# Sheet2.net
KiCad netlist of a schematic drawn in Altium Designer
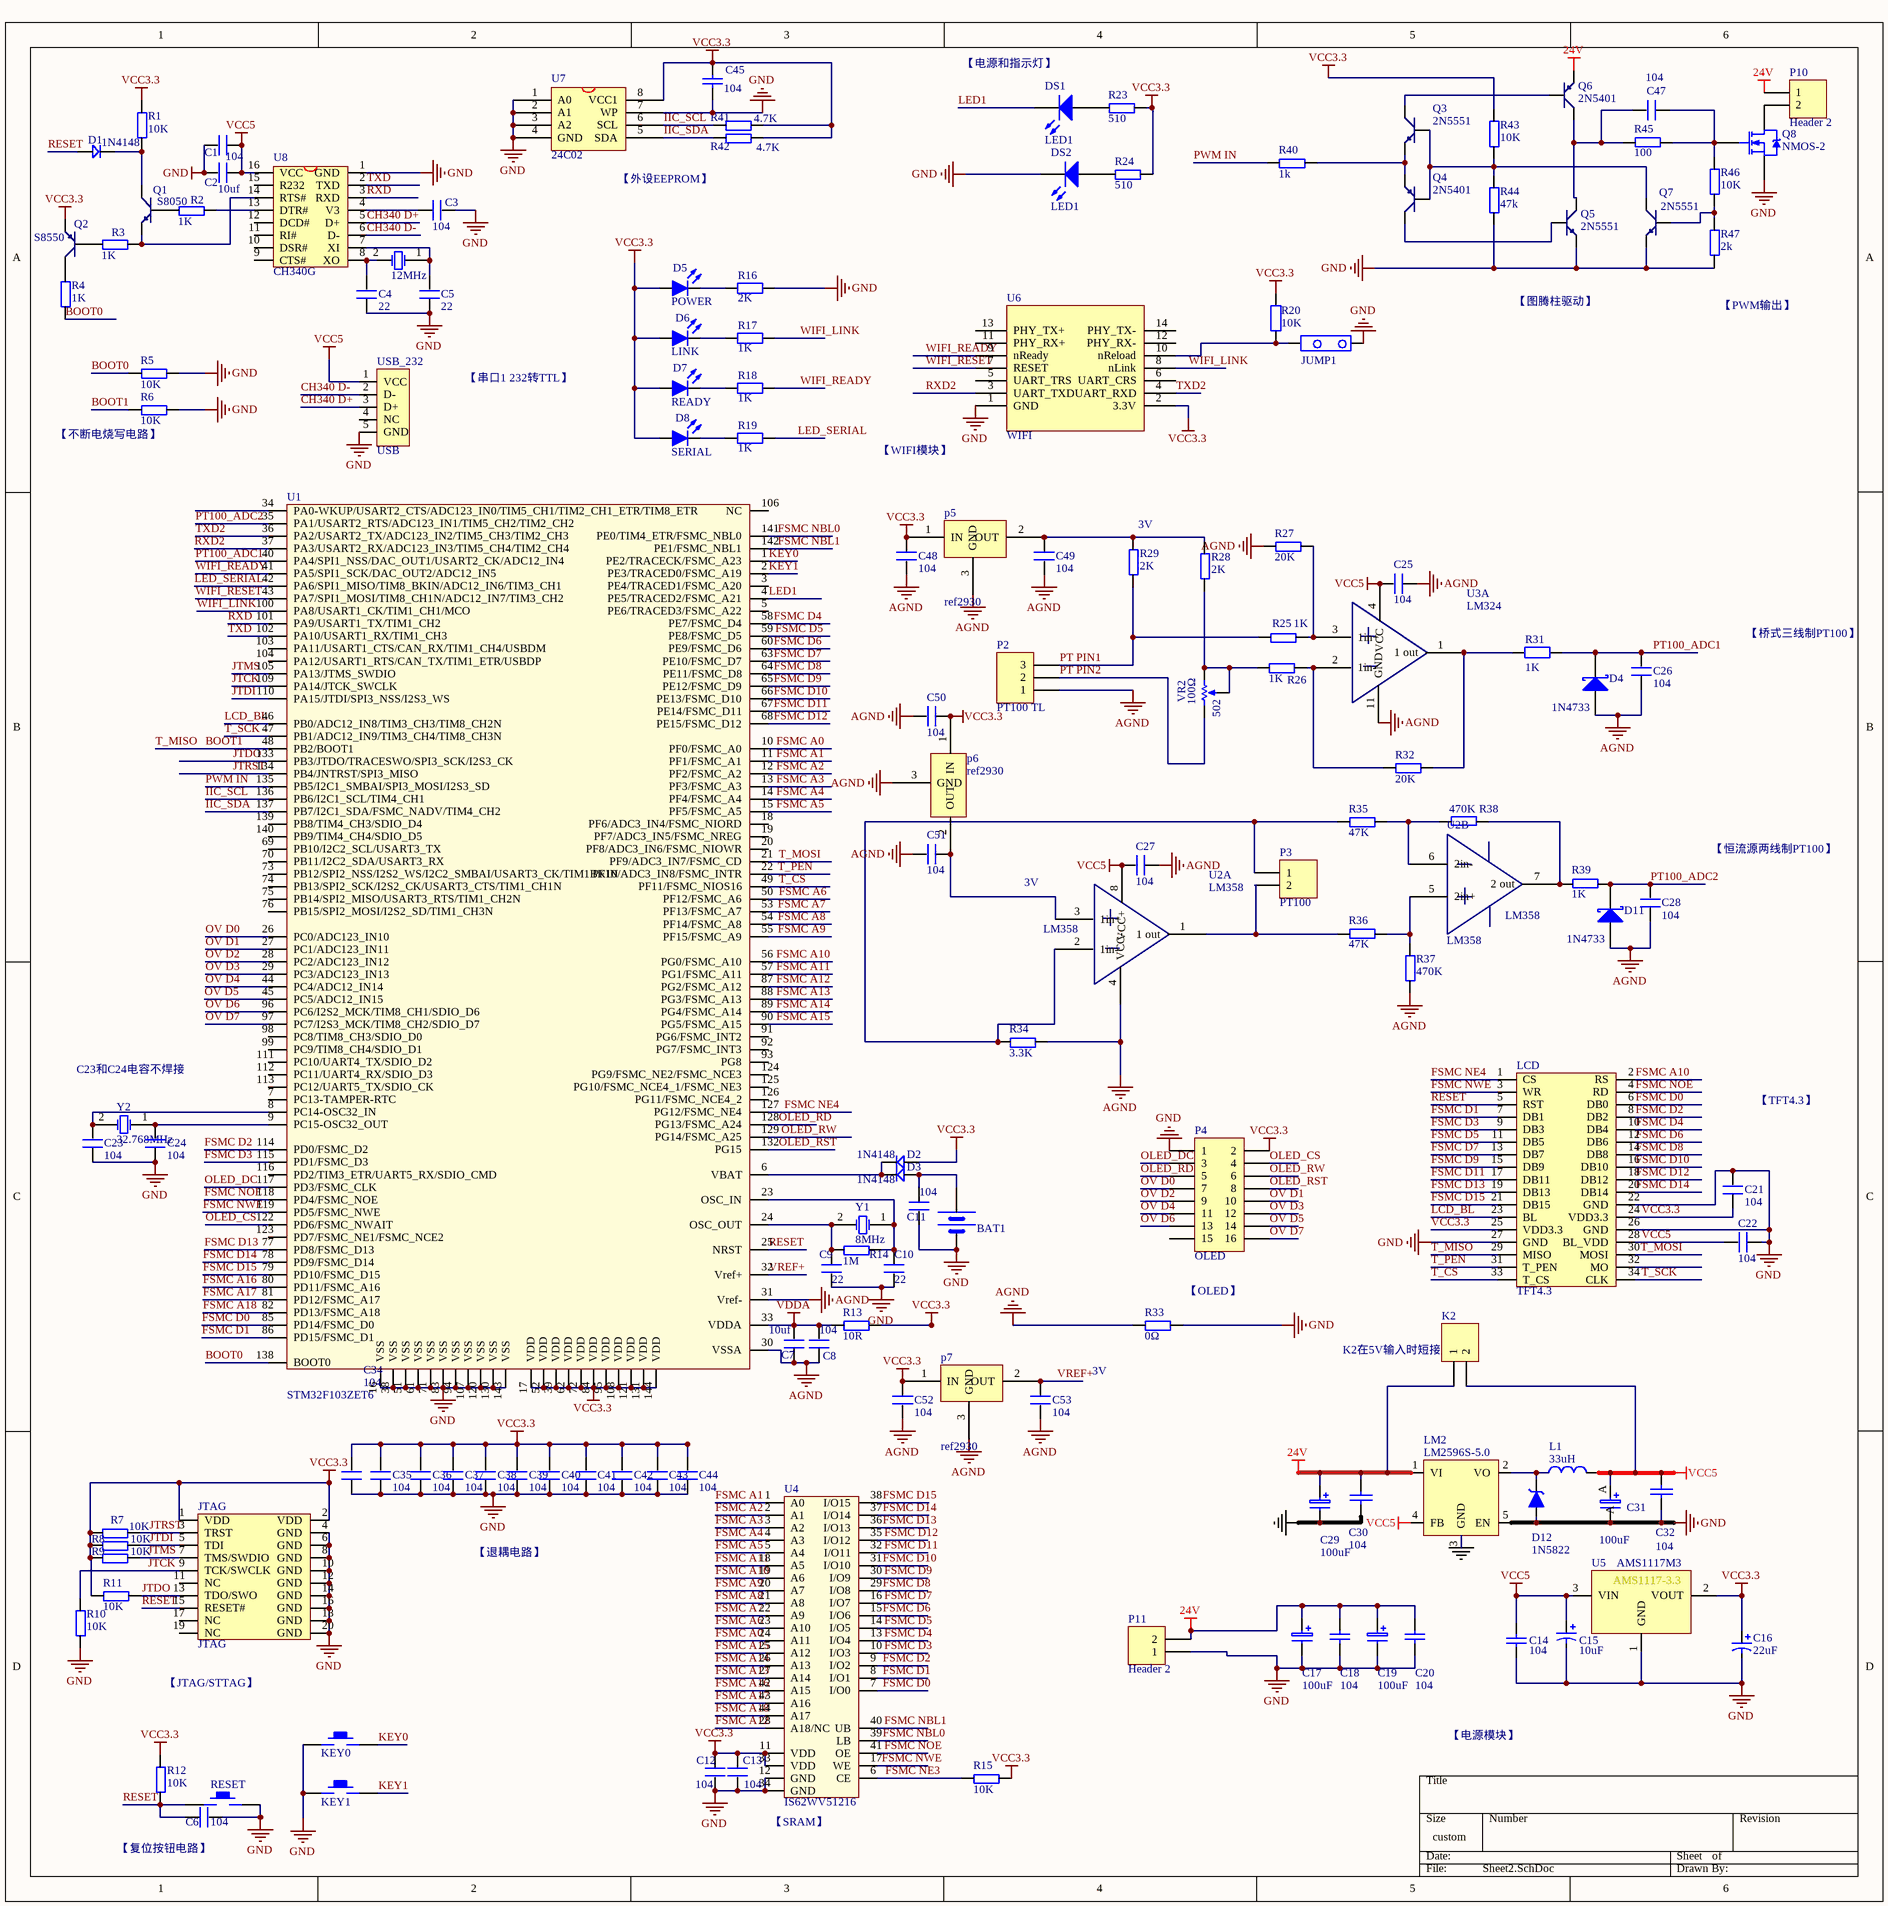
[diagram p0: Sheet2.SchDoc]

(export (version "E")
  (design (tool "Eeschema 10.0.6"))
  (components
    (comp (ref "BAT1") (value "BATT") (footprint "BATM") (libsource (lib "WARSHIP") (part "BAT")))
    (comp (ref "C1") (value "104") (footprint "0805") (libsource (lib "WARSHIP") (part "C")))
    (comp (ref "C2") (value "10uf") (footprint "0805") (libsource (lib "WARSHIP") (part "C")))
    (comp (ref "C3") (value "104") (footprint "0805") (libsource (lib "WARSHIP") (part "C")))
    (comp (ref "C4") (value "22") (footprint "0805") (libsource (lib "WARSHIP") (part "C")))
    (comp (ref "C5") (value "22") (footprint "0805") (libsource (lib "WARSHIP") (part "C")))
    (comp (ref "C6") (value "104") (footprint "0805") (libsource (lib "WARSHIP") (part "C")))
    (comp (ref "C7") (value "10uf") (footprint "0805") (libsource (lib "WARSHIP") (part "C")))
    (comp (ref "C8") (value "104") (footprint "0805") (libsource (lib "WARSHIP") (part "C")))
    (comp (ref "C9") (value "22") (footprint "0805") (libsource (lib "WARSHIP") (part "C")))
    (comp (ref "C10") (value "22") (footprint "0805") (libsource (lib "WARSHIP") (part "C")))
    (comp (ref "C11") (value "104") (footprint "0805") (libsource (lib "WARSHIP") (part "C")))
    (comp (ref "C12") (value "104") (footprint "0805") (libsource (lib "WARSHIP") (part "C")))
    (comp (ref "C13") (value "104") (footprint "0805") (libsource (lib "WARSHIP") (part "C")))
    (comp (ref "C14") (value "104") (footprint "0805") (libsource (lib "") (part "Cap1_1")))
    (comp (ref "C15")
      (value "10uF")
      (footprint "CASE-3216A")
      (libsource (lib "MySchematicLib") (part "Cap2"))
    )
    (comp (ref "C16")
      (value "22uF")
      (footprint "RVT 22UF 25V")
      (libsource (lib "MySchematicLib") (part "Cap2"))
    )
    (comp (ref "C17") (value "100uF") (footprint "CC8*10.5") (libsource (lib "MySchematicLib") (part "Cap3")))
    (comp (ref "C18") (value "104") (footprint "0805") (libsource (lib "MySchematicLib") (part "Cap1")))
    (comp (ref "C19") (value "100uF") (footprint "CC8*10.5") (libsource (lib "MySchematicLib") (part "Cap3")))
    (comp (ref "C20") (value "104") (footprint "0805") (libsource (lib "MySchematicLib") (part "Cap1")))
    (comp (ref "C21") (value "104") (footprint "0805") (libsource (lib "WARSHIP") (part "C")))
    (comp (ref "C22") (value "104") (footprint "0805") (libsource (lib "WARSHIP") (part "C")))
    (comp (ref "C23") (value "104") (footprint "0805") (libsource (lib "WARSHIP") (part "C")))
    (comp (ref "C24") (value "104") (footprint "0805") (libsource (lib "WARSHIP") (part "C")))
    (comp (ref "C25") (value "104") (footprint "0805") (libsource (lib "WARSHIP") (part "C")))
    (comp (ref "C26") (value "104") (footprint "0805") (libsource (lib "WARSHIP") (part "C")))
    (comp (ref "C27") (value "104") (footprint "0805") (libsource (lib "WARSHIP") (part "C")))
    (comp (ref "C28") (value "104") (footprint "0805") (libsource (lib "WARSHIP") (part "C")))
    (comp (ref "C29") (value "100uF") (footprint "CC8*10.5") (libsource (lib "MySchematicLib") (part "Cap3")))
    (comp (ref "C30") (value "104") (footprint "0805") (libsource (lib "*") (part "CAP")))
    (comp (ref "C31") (value "100uF") (footprint "rvt 100uf /25V") (libsource (lib "") (part "Cap3_1")))
    (comp (ref "C32") (value "104") (footprint "0805") (libsource (lib "") (part "CAP_1")))
    (comp (ref "C34") (value "104") (footprint "0805") (libsource (lib "WARSHIP") (part "C")))
    (comp (ref "C35") (value "104") (footprint "0805") (libsource (lib "WARSHIP") (part "C")))
    (comp (ref "C36") (value "104") (footprint "0805") (libsource (lib "WARSHIP") (part "C")))
    (comp (ref "C37") (value "104") (footprint "0805") (libsource (lib "WARSHIP") (part "C")))
    (comp (ref "C38") (value "104") (footprint "0805") (libsource (lib "WARSHIP") (part "C")))
    (comp (ref "C39") (value "104") (footprint "0805") (libsource (lib "WARSHIP") (part "C")))
    (comp (ref "C40") (value "104") (footprint "0805") (libsource (lib "WARSHIP") (part "C")))
    (comp (ref "C41") (value "104") (footprint "0805") (libsource (lib "WARSHIP") (part "C")))
    (comp (ref "C42") (value "104") (footprint "0805") (libsource (lib "WARSHIP") (part "C")))
    (comp (ref "C43") (value "104") (footprint "0805") (libsource (lib "WARSHIP") (part "C")))
    (comp (ref "C44") (value "104") (footprint "0805") (libsource (lib "WARSHIP") (part "C")))
    (comp (ref "C45")
      (value "104")
      (footprint "0805")
      (description "Capacitor")
      (fields (field (name "Comment") "Cap") (field (name "PUBLISHER") "Altium Limited"))
      (libsource (lib "Miscellaneous Devices") (part "Cap"))
    )
    (comp (ref "C47") (value "104") (footprint "0805") (libsource (lib "WARSHIP") (part "C")))
    (comp (ref "C48") (value "104") (footprint "0805") (libsource (lib "WARSHIP") (part "C")))
    (comp (ref "C49") (value "104") (footprint "0805") (libsource (lib "WARSHIP") (part "C")))
    (comp (ref "C50") (value "104") (footprint "0805") (libsource (lib "WARSHIP") (part "C")))
    (comp (ref "C51") (value "104") (footprint "0805") (libsource (lib "WARSHIP") (part "C")))
    (comp (ref "C52") (value "104") (footprint "0805") (libsource (lib "WARSHIP") (part "C")))
    (comp (ref "C53") (value "104") (footprint "0805") (libsource (lib "WARSHIP") (part "C")))
    (comp (ref "D1") (value "1N4148") (footprint "DIODE_SOP") (libsource (lib "WARSHIP") (part "D")))
    (comp (ref "D2") (value "1N4148") (footprint "DIODE_SOP") (libsource (lib "WARSHIP") (part "D")))
    (comp (ref "D3") (value "1N4148") (footprint "DIODE_SOP") (libsource (lib "WARSHIP") (part "D")))
    (comp (ref "D4")
      (value "1N4733")
      (footprint "LC-DO-41")
      (description "Schottky Rectifier")
      (fields (field (name "PUBLISHER") "Altium Limited"))
      (libsource (lib "") (part "Diode 18TQ045_1"))
    )
    (comp (ref "D5") (value "POWER") (footprint "SMDLED") (libsource (lib "MySchematicLib") (part "LED1")))
    (comp (ref "D6") (value "LINK") (footprint "SMDLED") (libsource (lib "MySchematicLib") (part "LED1")))
    (comp (ref "D7") (value "READY") (footprint "SMDLED") (libsource (lib "MySchematicLib") (part "LED1")))
    (comp (ref "D8") (value "SERIAL") (footprint "SMDLED") (libsource (lib "MySchematicLib") (part "LED1")))
    (comp (ref "D11")
      (value "1N4733")
      (footprint "LC-DO-41")
      (description "Schottky Rectifier")
      (fields (field (name "PUBLISHER") "Altium Limited"))
      (libsource (lib "Miscellaneous Devices") (part "Diode 18TQ045"))
    )
    (comp (ref "D12")
      (value "1N5822")
      (footprint "1n5822")
      (description "Zener Diode")
      (libsource (lib "*") (part "ZENER3"))
    )
    (comp (ref "DS1")
      (value "LED1")
      (footprint "SMDLED")
      (description "Typical RED, GREEN, YELLOW, AMBER GaAs LED")
      (fields (field (name "PUBLISHER") "Altium Limited"))
      (libsource (lib "WARSHIP") (part "LED2"))
    )
    (comp (ref "DS2")
      (value "LED1")
      (footprint "SMDLED")
      (description "Typical RED, GREEN, YELLOW, AMBER GaAs LED")
      (fields (field (name "PUBLISHER") "Altium Limited"))
      (libsource (lib "WARSHIP") (part "LED2"))
    )
    (comp (ref "JTAG") (value "JTAG") (footprint "JTAG_20") (libsource (lib "WARSHIP") (part "JTAG")))
    (comp (ref "JUMP1")
      (value "Jumper")
      (footprint "HDR1X2")
      (libsource (lib "MySchematicLib") (part "Jumper"))
    )
    (comp (ref "K2")
      (value "Header 2")
      (footprint "HDR1X2")
      (description "Header, 2-Pin")
      (fields (field (name "PUBLISHER") "Altium Limited"))
      (libsource (lib "") (part "Header 2_2"))
    )
    (comp (ref "KEY0") (value "KEY_M") (footprint "KEY_M") (libsource (lib "WARSHIP") (part "KEY_M")))
    (comp (ref "KEY1") (value "KEY_M") (footprint "KEY_M") (libsource (lib "WARSHIP") (part "KEY_M")))
    (comp (ref "L1") (value "33uH") (footprint "100UH") (libsource (lib "*") (part "L")))
    (comp (ref "LCD")
      (value "TFT4.3")
      (footprint "DB2*17-3.5")
      (libsource (lib "4.3TFTLCD") (part "TFT_LCD2"))
    )
    (comp (ref "LM2") (value "LM2596S-5.0") (footprint "LM2596S-5.0") (libsource (lib "*") (part "12V-5V")))
    (comp (ref "P2")
      (value "PT100 TL")
      (footprint "3SPI")
      (description "Header, 3-Pin")
      (fields (field (name "PUBLISHER") "Altium Limited"))
      (libsource (lib "Miscellaneous Connectors") (part "Header 3"))
    )
    (comp (ref "P3")
      (value "PT100")
      (footprint "2SPI")
      (description "Header, 2-Pin")
      (fields (field (name "PUBLISHER") "Altium Limited"))
      (libsource (lib "") (part "Header 2_1"))
    )
    (comp (ref "P4")
      (value "OLED")
      (footprint "HDR2X8")
      (description "Header, 8-Pin, Dual row")
      (fields (field (name "PUBLISHER") "Altium Limited"))
      (libsource (lib "OLED模块封装库") (part "Header 8X2"))
    )
    (comp (ref "p5")
      (value "ref2930")
      (footprint "LC-SOT-23(SOT-23-3)")
      (libsource (lib "ref2930aid") (part "ref2930"))
    )
    (comp (ref "p6")
      (value "ref2930")
      (footprint "LC-SOT-23(SOT-23-3)")
      (libsource (lib "") (part "ref2930_1"))
    )
    (comp (ref "p7")
      (value "ref2930")
      (footprint "LC-SOT-23(SOT-23-3)")
      (libsource (lib "ref2930aid") (part "ref2930"))
    )
    (comp (ref "P10")
      (value "Header 2")
      (footprint "2SPI")
      (description "Header, 2-Pin")
      (fields (field (name "PUBLISHER") "Altium Limited"))
      (libsource (lib "") (part "Header 2_1"))
    )
    (comp (ref "P11")
      (value "Header 2")
      (footprint "2SPI")
      (description "Header, 2-Pin")
      (fields (field (name "PUBLISHER") "Altium Limited"))
      (libsource (lib "Miscellaneous Connectors") (part "Header 2"))
    )
    (comp (ref "Q1")
      (value "S8050")
      (footprint "SOT-23R")
      (description "8050/BCW846/BCW847")
      (libsource (lib "WARSHIP") (part "NPN"))
    )
    (comp (ref "Q2")
      (value "S8550")
      (footprint "SOT-23R")
      (description "8550/BCW68")
      (libsource (lib "WARSHIP") (part "PNP"))
    )
    (comp (ref "Q3")
      (value "2N5551")
      (footprint "SOT-23R")
      (description "8050/BCW846/BCW847")
      (libsource (lib "WARSHIP") (part "NPN"))
    )
    (comp (ref "Q4")
      (value "2N5401")
      (footprint "SOT-23R")
      (description "8550/BCW68")
      (libsource (lib "WARSHIP") (part "PNP"))
    )
    (comp (ref "Q5")
      (value "2N5551")
      (footprint "SOT-23R")
      (description "8050/BCW846/BCW847")
      (libsource (lib "WARSHIP") (part "NPN"))
    )
    (comp (ref "Q6")
      (value "2N5401")
      (footprint "SOT-23R")
      (description "8550/BCW68")
      (libsource (lib "WARSHIP") (part "PNP"))
    )
    (comp (ref "Q7")
      (value "2N5551")
      (footprint "SOT-23R")
      (description "8050/BCW846/BCW847")
      (libsource (lib "WARSHIP") (part "NPN"))
    )
    (comp (ref "Q8")
      (value "NMOS-2")
      (footprint "LC-TO-263-2")
      (description "N-Channel Power MOSFET")
      (fields (field (name "PUBLISHER") "Altium Limited"))
      (libsource (lib "Miscellaneous Devices") (part "NMOS-2"))
    )
    (comp (ref "R1") (value "10K") (footprint "0805") (libsource (lib "WARSHIP") (part "R")))
    (comp (ref "R2") (value "1K") (footprint "0805") (libsource (lib "WARSHIP") (part "R")))
    (comp (ref "R3") (value "1K") (footprint "0805") (libsource (lib "WARSHIP") (part "R")))
    (comp (ref "R4") (value "1K") (footprint "0805") (libsource (lib "WARSHIP") (part "R")))
    (comp (ref "R5") (value "10K") (footprint "0805") (libsource (lib "WARSHIP") (part "R")))
    (comp (ref "R6") (value "10K") (footprint "0805") (libsource (lib "WARSHIP") (part "R")))
    (comp (ref "R7") (value "10K") (footprint "0805") (libsource (lib "WARSHIP") (part "R")))
    (comp (ref "R8") (value "10K") (footprint "0805") (libsource (lib "WARSHIP") (part "R")))
    (comp (ref "R9") (value "10K") (footprint "0805") (libsource (lib "WARSHIP") (part "R")))
    (comp (ref "R10") (value "10K") (footprint "0805") (libsource (lib "WARSHIP") (part "R")))
    (comp (ref "R11") (value "10K") (footprint "0805") (libsource (lib "WARSHIP") (part "R")))
    (comp (ref "R12") (value "10K") (footprint "0805") (libsource (lib "WARSHIP") (part "R")))
    (comp (ref "R13") (value "10R") (footprint "0805") (libsource (lib "WARSHIP") (part "R")))
    (comp (ref "R14") (value "1M") (footprint "0805") (libsource (lib "WARSHIP") (part "R")))
    (comp (ref "R15") (value "10K") (footprint "0805") (libsource (lib "WARSHIP") (part "R")))
    (comp (ref "R16") (value "2K") (footprint "0805") (libsource (lib "") (part "Res1_1")))
    (comp (ref "R17") (value "1K") (footprint "0805") (libsource (lib "") (part "Res1_1")))
    (comp (ref "R18") (value "1K") (footprint "0805") (libsource (lib "") (part "Res1_1")))
    (comp (ref "R19") (value "1K") (footprint "0805") (libsource (lib "") (part "Res1_1")))
    (comp (ref "R20") (value "10K") (footprint "0805") (libsource (lib "MySchematicLib") (part "Res1")))
    (comp (ref "R23") (value "510") (footprint "0805") (libsource (lib "WARSHIP") (part "R")))
    (comp (ref "R24") (value "510") (footprint "0805") (libsource (lib "WARSHIP") (part "R")))
    (comp (ref "R25") (value "1K") (footprint "0805") (libsource (lib "WARSHIP") (part "R")))
    (comp (ref "R26") (value "1K") (footprint "0805") (libsource (lib "WARSHIP") (part "R")))
    (comp (ref "R27") (value "20K") (footprint "0805") (libsource (lib "WARSHIP") (part "R")))
    (comp (ref "R28") (value "2K") (footprint "0805") (libsource (lib "WARSHIP") (part "R")))
    (comp (ref "R29") (value "2K") (footprint "0805") (libsource (lib "WARSHIP") (part "R")))
    (comp (ref "R31")
      (value "1K")
      (footprint "0805")
      (description "Resistor")
      (fields (field (name "Comment") "Res2") (field (name "PUBLISHER") "Altium Limited"))
      (libsource (lib "Miscellaneous Devices") (part "Res2"))
    )
    (comp (ref "R32") (value "20K") (footprint "0805") (libsource (lib "WARSHIP") (part "R")))
    (comp (ref "R33") (value "0Ω") (footprint "0805") (libsource (lib "WARSHIP") (part "R")))
    (comp (ref "R34") (value "3.3K") (footprint "0805") (libsource (lib "WARSHIP") (part "R")))
    (comp (ref "R35") (value "47K") (footprint "0805") (libsource (lib "WARSHIP") (part "R")))
    (comp (ref "R36") (value "47K") (footprint "0805") (libsource (lib "WARSHIP") (part "R")))
    (comp (ref "R37") (value "470K") (footprint "0805") (libsource (lib "WARSHIP") (part "R")))
    (comp (ref "R38") (value "470K") (footprint "0805") (libsource (lib "WARSHIP") (part "R")))
    (comp (ref "R39") (value "1K") (footprint "0805") (libsource (lib "WARSHIP") (part "R")))
    (comp (ref "R40") (value "1k") (footprint "0805") (libsource (lib "WARSHIP") (part "R")))
    (comp (ref "R41") (value "4.7K") (footprint "0805") (libsource (lib "WARSHIP") (part "R")))
    (comp (ref "R42") (value "4.7K") (footprint "0805") (libsource (lib "WARSHIP") (part "R")))
    (comp (ref "R43") (value "10K") (footprint "0805") (libsource (lib "WARSHIP") (part "R")))
    (comp (ref "R44") (value "47k") (footprint "0805") (libsource (lib "WARSHIP") (part "R")))
    (comp (ref "R45") (value "100") (footprint "0805") (libsource (lib "WARSHIP") (part "R")))
    (comp (ref "R46") (value "10K") (footprint "0805") (libsource (lib "WARSHIP") (part "R")))
    (comp (ref "R47") (value "2k") (footprint "0805") (libsource (lib "WARSHIP") (part "R")))
    (comp (ref "RESET") (value "KEY_M") (footprint "KEY_M") (libsource (lib "WARSHIP") (part "KEY_M")))
    (comp (ref "U1")
      (value "STM32F103ZET6")
      (footprint "LQFP144")
      (libsource (lib "WARSHIP") (part "STM32F103ZET6"))
    )
    (comp (ref "U2") (value "LM358") (footprint "LC-MSOP-8") (libsource (lib "LM358") (part "LM358")))
    (comp (ref "U3") (value "LM324") (footprint "LC-DIP-14") (libsource (lib "LM324") (part "LM324")))
    (comp (ref "U4")
      (value "IS62WV51216")
      (footprint "TSOP44")
      (libsource (lib "WARSHIP") (part "IS61LV51216"))
    )
    (comp (ref "U5")
      (value "AMS1117M3")
      (footprint "LC-SOT-223")
      (libsource (lib "MySchematicLib") (part "AMS1117-3.3"))
    )
    (comp (ref "U6")
      (value "WIFI")
      (footprint "USR-WIFI232")
      (libsource (lib "Communication Module") (part "USR-WIFI232-ABD"))
    )
    (comp (ref "U7") (value "24C02") (footprint "SOP-8") (libsource (lib "WARSHIP") (part "24C256")))
    (comp (ref "U8")
      (value "CH340G")
      (footprint "SOP16M")
      (description "USB2UART")
      (libsource (lib "WARSHIP") (part "CH340G"))
    )
    (comp (ref "USB_232") (value "USB") (footprint "USB/SM0.8-6H5") (libsource (lib "WARSHIP") (part "USB5")))
    (comp (ref "VR2")
      (value "502")
      (footprint "503")
      (description "Potentiometer")
      (fields (field (name "ALTIUM_VALUE") "100Ω") (field (name "PUBLISHER") "Altium Limited"))
      (libsource (lib "Miscellaneous Devices") (part "RPot"))
    )
    (comp (ref "Y1")
      (value "8MHz")
      (footprint "XTAL_US")
      (description "Crystal Oscillator")
      (fields (field (name "PUBLISHER") "Altium Limited"))
      (libsource (lib "WARSHIP") (part "XTAL"))
    )
    (comp (ref "Y2")
      (value "32.768MHz")
      (footprint "XTAL32")
      (description "Crystal Oscillator")
      (fields (field (name "PUBLISHER") "Altium Limited"))
      (libsource (lib "WARSHIP") (part "XTAL"))
    )
    (comp (ref "Y3")
      (value "12MHz")
      (footprint "XTAL_US")
      (description "Crystal Oscillator")
      (fields (field (name "PUBLISHER") "Altium Limited"))
      (libsource (lib "WARSHIP") (part "XTAL"))
    )
  )
  (nets
    (net (code "1") (name "/BOOT0") (class "Default")
      (node (ref "R4") (pin "1") (pintype "passive"))
      (node (ref "R5") (pin "1") (pintype "passive"))
      (node (ref "U1") (pin "138") (pinfunction "BOOT0_138") (pintype "passive"))
    )
    (net (code "2") (name "/BOOT1") (class "Default")
      (node (ref "LCD") (pin "29") (pinfunction "MISO_29") (pintype "passive"))
      (node (ref "R6") (pin "1") (pintype "passive"))
      (node (ref "U1") (pin "48") (pinfunction "PB2/BOOT1_48") (pintype "passive"))
    )
    (net (code "3") (name "/CH340 D+") (class "Default")
      (node (ref "U8") (pin "5") (pinfunction "D+_5") (pintype "passive"))
      (node (ref "USB_232") (pin "3") (pinfunction "D+_3") (pintype "passive"))
    )
    (net (code "4") (name "/CH340 D-") (class "Default")
      (node (ref "U8") (pin "6") (pinfunction "D-_6") (pintype "passive"))
      (node (ref "USB_232") (pin "2") (pinfunction "D-_2") (pintype "passive"))
    )
    (net (code "5") (name "/FSMC A0") (class "Default")
      (node (ref "U1") (pin "10") (pinfunction "PF0/FSMC_A0_10") (pintype "passive"))
      (node (ref "U4") (pin "24") (pinfunction "A11_24") (pintype "passive"))
    )
    (net (code "6") (name "/FSMC A1") (class "Default")
      (node (ref "U1") (pin "11") (pinfunction "PF1/FSMC_A1_11") (pintype "passive"))
      (node (ref "U4") (pin "1") (pinfunction "A0_1") (pintype "passive"))
    )
    (net (code "7") (name "/FSMC A2") (class "Default")
      (node (ref "U1") (pin "12") (pinfunction "PF2/FSMC_A2_12") (pintype "passive"))
      (node (ref "U4") (pin "2") (pinfunction "A1_2") (pintype "passive"))
    )
    (net (code "8") (name "/FSMC A3") (class "Default")
      (node (ref "U1") (pin "13") (pinfunction "PF3/FSMC_A3_13") (pintype "passive"))
      (node (ref "U4") (pin "3") (pinfunction "A2_3") (pintype "passive"))
    )
    (net (code "9") (name "/FSMC A4") (class "Default")
      (node (ref "U1") (pin "14") (pinfunction "PF4/FSMC_A4_14") (pintype "passive"))
      (node (ref "U4") (pin "4") (pinfunction "A3_4") (pintype "passive"))
    )
    (net (code "10") (name "/FSMC A5") (class "Default")
      (node (ref "U1") (pin "15") (pinfunction "PF5/FSMC_A5_15") (pintype "passive"))
      (node (ref "U4") (pin "5") (pinfunction "A4_5") (pintype "passive"))
    )
    (net (code "11") (name "/FSMC A6") (class "Default")
      (node (ref "U1") (pin "50") (pinfunction "PF12/FSMC_A6_50") (pintype "passive"))
      (node (ref "U4") (pin "23") (pinfunction "A10_23") (pintype "passive"))
    )
    (net (code "12") (name "/FSMC A7") (class "Default")
      (node (ref "U1") (pin "53") (pinfunction "PF13/FSMC_A7_53") (pintype "passive"))
      (node (ref "U4") (pin "22") (pinfunction "A9_22") (pintype "passive"))
    )
    (net (code "13") (name "/FSMC A8") (class "Default")
      (node (ref "U1") (pin "54") (pinfunction "PF14/FSMC_A8_54") (pintype "passive"))
      (node (ref "U4") (pin "21") (pinfunction "A8_21") (pintype "passive"))
    )
    (net (code "14") (name "/FSMC A9") (class "Default")
      (node (ref "U1") (pin "55") (pinfunction "PF15/FSMC_A9_55") (pintype "passive"))
      (node (ref "U4") (pin "20") (pinfunction "A7_20") (pintype "passive"))
    )
    (net (code "15") (name "/FSMC A10") (class "Default")
      (node (ref "LCD") (pin "2") (pinfunction "RS_2") (pintype "passive"))
      (node (ref "U1") (pin "56") (pinfunction "PG0/FSMC_A10_56") (pintype "passive"))
      (node (ref "U4") (pin "19") (pinfunction "A6_19") (pintype "passive"))
    )
    (net (code "16") (name "/FSMC A11") (class "Default")
      (node (ref "U1") (pin "57") (pinfunction "PG1/FSMC_A11_57") (pintype "passive"))
      (node (ref "U4") (pin "18") (pinfunction "A5_18") (pintype "passive"))
    )
    (net (code "17") (name "/FSMC A12") (class "Default")
      (node (ref "U1") (pin "87") (pinfunction "PG2/FSMC_A12_87") (pintype "passive"))
      (node (ref "U4") (pin "28") (pinfunction "A18/NC_28") (pintype "passive"))
    )
    (net (code "18") (name "/FSMC A13") (class "Default")
      (node (ref "U1") (pin "88") (pinfunction "PG3/FSMC_A13_88") (pintype "passive"))
      (node (ref "U4") (pin "27") (pinfunction "A14_27") (pintype "passive"))
    )
    (net (code "19") (name "/FSMC A14") (class "Default")
      (node (ref "U1") (pin "89") (pinfunction "PG4/FSMC_A14_89") (pintype "passive"))
      (node (ref "U4") (pin "26") (pinfunction "A13_26") (pintype "passive"))
    )
    (net (code "20") (name "/FSMC A15") (class "Default")
      (node (ref "U1") (pin "90") (pinfunction "PG5/FSMC_A15_90") (pintype "passive"))
      (node (ref "U4") (pin "25") (pinfunction "A12_25") (pintype "passive"))
    )
    (net (code "21") (name "/FSMC A16") (class "Default")
      (node (ref "U1") (pin "80") (pinfunction "PD11/FSMC_A16_80") (pintype "passive"))
      (node (ref "U4") (pin "42") (pinfunction "A15_42") (pintype "passive"))
    )
    (net (code "22") (name "/FSMC A17") (class "Default")
      (node (ref "U1") (pin "81") (pinfunction "PD12/FSMC_A17_81") (pintype "passive"))
      (node (ref "U4") (pin "43") (pinfunction "A16_43") (pintype "passive"))
    )
    (net (code "23") (name "/FSMC A18") (class "Default")
      (node (ref "U1") (pin "82") (pinfunction "PD13/FSMC_A18_82") (pintype "passive"))
      (node (ref "U4") (pin "44") (pinfunction "A17_44") (pintype "passive"))
    )
    (net (code "24") (name "/FSMC D0") (class "Default")
      (node (ref "LCD") (pin "6") (pinfunction "DB0_6") (pintype "passive"))
      (node (ref "U1") (pin "85") (pinfunction "PD14/FSMC_D0_85") (pintype "passive"))
      (node (ref "U4") (pin "7") (pinfunction "I/O0_7") (pintype "passive"))
    )
    (net (code "25") (name "/FSMC D1") (class "Default")
      (node (ref "LCD") (pin "7") (pinfunction "DB1_7") (pintype "passive"))
      (node (ref "U1") (pin "86") (pinfunction "PD15/FSMC_D1_86") (pintype "passive"))
      (node (ref "U4") (pin "8") (pinfunction "I/O1_8") (pintype "passive"))
    )
    (net (code "26") (name "/FSMC D2") (class "Default")
      (node (ref "LCD") (pin "8") (pinfunction "DB2_8") (pintype "passive"))
      (node (ref "U1") (pin "114") (pinfunction "PD0/FSMC_D2_114") (pintype "passive"))
      (node (ref "U4") (pin "9") (pinfunction "I/O2_9") (pintype "passive"))
    )
    (net (code "27") (name "/FSMC D3") (class "Default")
      (node (ref "LCD") (pin "9") (pinfunction "DB3_9") (pintype "passive"))
      (node (ref "U1") (pin "115") (pinfunction "PD1/FSMC_D3_115") (pintype "passive"))
      (node (ref "U4") (pin "10") (pinfunction "I/O3_10") (pintype "passive"))
    )
    (net (code "28") (name "/FSMC D4") (class "Default")
      (node (ref "LCD") (pin "10") (pinfunction "DB4_10") (pintype "passive"))
      (node (ref "U1") (pin "58") (pinfunction "PE7/FSMC_D4_58") (pintype "passive"))
      (node (ref "U4") (pin "13") (pinfunction "I/O4_13") (pintype "passive"))
    )
    (net (code "29") (name "/FSMC D5") (class "Default")
      (node (ref "LCD") (pin "11") (pinfunction "DB5_11") (pintype "passive"))
      (node (ref "U1") (pin "59") (pinfunction "PE8/FSMC_D5_59") (pintype "passive"))
      (node (ref "U4") (pin "14") (pinfunction "I/O5_14") (pintype "passive"))
    )
    (net (code "30") (name "/FSMC D6") (class "Default")
      (node (ref "LCD") (pin "12") (pinfunction "DB6_12") (pintype "passive"))
      (node (ref "U1") (pin "60") (pinfunction "PE9/FSMC_D6_60") (pintype "passive"))
      (node (ref "U4") (pin "15") (pinfunction "I/O6_15") (pintype "passive"))
    )
    (net (code "31") (name "/FSMC D7") (class "Default")
      (node (ref "LCD") (pin "13") (pinfunction "DB7_13") (pintype "passive"))
      (node (ref "U1") (pin "63") (pinfunction "PE10/FSMC_D7_63") (pintype "passive"))
      (node (ref "U4") (pin "16") (pinfunction "I/O7_16") (pintype "passive"))
    )
    (net (code "32") (name "/FSMC D8") (class "Default")
      (node (ref "LCD") (pin "14") (pinfunction "DB8_14") (pintype "passive"))
      (node (ref "U1") (pin "64") (pinfunction "PE11/FSMC_D8_64") (pintype "passive"))
      (node (ref "U4") (pin "29") (pinfunction "I/O8_29") (pintype "passive"))
    )
    (net (code "33") (name "/FSMC D9") (class "Default")
      (node (ref "LCD") (pin "15") (pinfunction "DB9_15") (pintype "passive"))
      (node (ref "U1") (pin "65") (pinfunction "PE12/FSMC_D9_65") (pintype "passive"))
      (node (ref "U4") (pin "30") (pinfunction "I/O9_30") (pintype "passive"))
    )
    (net (code "34") (name "/FSMC D10") (class "Default")
      (node (ref "LCD") (pin "16") (pinfunction "DB10_16") (pintype "passive"))
      (node (ref "U1") (pin "66") (pinfunction "PE13/FSMC_D10_66") (pintype "passive"))
      (node (ref "U4") (pin "31") (pinfunction "I/O10_31") (pintype "passive"))
    )
    (net (code "35") (name "/FSMC D11") (class "Default")
      (node (ref "LCD") (pin "17") (pinfunction "DB11_17") (pintype "passive"))
      (node (ref "U1") (pin "67") (pinfunction "PE14/FSMC_D11_67") (pintype "passive"))
      (node (ref "U4") (pin "32") (pinfunction "I/O11_32") (pintype "passive"))
    )
    (net (code "36") (name "/FSMC D12") (class "Default")
      (node (ref "LCD") (pin "18") (pinfunction "DB12_18") (pintype "passive"))
      (node (ref "U1") (pin "68") (pinfunction "PE15/FSMC_D12_68") (pintype "passive"))
      (node (ref "U4") (pin "35") (pinfunction "I/O12_35") (pintype "passive"))
    )
    (net (code "37") (name "/FSMC D13") (class "Default")
      (node (ref "LCD") (pin "19") (pinfunction "DB13_19") (pintype "passive"))
      (node (ref "U1") (pin "77") (pinfunction "PD8/FSMC_D13_77") (pintype "passive"))
      (node (ref "U4") (pin "36") (pinfunction "I/O13_36") (pintype "passive"))
    )
    (net (code "38") (name "/FSMC D14") (class "Default")
      (node (ref "LCD") (pin "20") (pinfunction "DB14_20") (pintype "passive"))
      (node (ref "U1") (pin "78") (pinfunction "PD9/FSMC_D14_78") (pintype "passive"))
      (node (ref "U4") (pin "37") (pinfunction "I/O14_37") (pintype "passive"))
    )
    (net (code "39") (name "/FSMC D15") (class "Default")
      (node (ref "LCD") (pin "21") (pinfunction "DB15_21") (pintype "passive"))
      (node (ref "U1") (pin "79") (pinfunction "PD10/FSMC_D15_79") (pintype "passive"))
      (node (ref "U4") (pin "38") (pinfunction "I/O15_38") (pintype "passive"))
    )
    (net (code "40") (name "/FSMC NBL0") (class "Default")
      (node (ref "U1") (pin "141") (pinfunction "PE0/TIM4_ETR/FSMC_NBL0_141") (pintype "passive"))
      (node (ref "U4") (pin "39") (pinfunction "LB_39") (pintype "passive"))
    )
    (net (code "41") (name "/FSMC NBL1") (class "Default")
      (node (ref "U1") (pin "142") (pinfunction "PE1/FSMC_NBL1_142") (pintype "passive"))
      (node (ref "U4") (pin "40") (pinfunction "UB_40") (pintype "passive"))
    )
    (net (code "42") (name "/FSMC NE3") (class "Default")
      (node (ref "R15") (pin "1") (pintype "passive"))
      (node (ref "U4") (pin "6") (pinfunction "CE_6") (pintype "passive"))
    )
    (net (code "43") (name "/FSMC NE4") (class "Default")
      (node (ref "LCD") (pin "1") (pinfunction "CS_1") (pintype "passive"))
      (node (ref "U1") (pin "127") (pinfunction "PG12/FSMC_NE4_127") (pintype "passive"))
    )
    (net (code "44") (name "/FSMC NOE") (class "Default")
      (node (ref "LCD") (pin "4") (pinfunction "RD_4") (pintype "passive"))
      (node (ref "U1") (pin "118") (pinfunction "PD4/FSMC_NOE_118") (pintype "passive"))
      (node (ref "U4") (pin "41") (pinfunction "OE_41") (pintype "passive"))
    )
    (net (code "45") (name "/FSMC NWE") (class "Default")
      (node (ref "LCD") (pin "3") (pinfunction "WR_3") (pintype "passive"))
      (node (ref "U1") (pin "119") (pinfunction "PD5/FSMC_NWE_119") (pintype "passive"))
      (node (ref "U4") (pin "17") (pinfunction "WE_17") (pintype "passive"))
    )
    (net (code "46") (name "/IIC_SCL") (class "Default")
      (node (ref "R41") (pin "1") (pintype "passive"))
      (node (ref "U1") (pin "136") (pinfunction "PB6/I2C1_SCL/TIM4_CH1_136") (pintype "passive"))
      (node (ref "U7") (pin "6") (pinfunction "SCL_6") (pintype "passive"))
    )
    (net (code "47") (name "/IIC_SDA") (class "Default")
      (node (ref "R42") (pin "1") (pintype "passive"))
      (node (ref "U1") (pin "137") (pinfunction "PB7/I2C1_SDA/FSMC_NADV/TIM4_CH2_137") (pintype "passive"))
      (node (ref "U7") (pin "5") (pinfunction "SDA_5") (pintype "passive"))
    )
    (net (code "48") (name "/JTCK") (class "Default")
      (node (ref "JTAG") (pin "9") (pinfunction "TCK/SWCLK_9") (pintype "passive"))
      (node (ref "R10") (pin "2") (pintype "passive"))
      (node (ref "U1") (pin "109") (pinfunction "PA14/JTCK_SWCLK_109") (pintype "passive"))
    )
    (net (code "49") (name "/JTDI") (class "Default")
      (node (ref "JTAG") (pin "5") (pinfunction "TDI_5") (pintype "passive"))
      (node (ref "R8") (pin "2") (pintype "passive"))
      (node (ref "U1") (pin "110") (pinfunction "PA15/JTDI/SPI3_NSS/I2S3_WS_110") (pintype "passive"))
    )
    (net (code "50") (name "/JTDO") (class "Default")
      (node (ref "JTAG") (pin "13") (pinfunction "TDO/SWO_13") (pintype "passive"))
      (node (ref "R11") (pin "2") (pintype "passive"))
      (node (ref "U1") (pin "133") (pinfunction "PB3/JTDO/TRACESWO/SPI3_SCK/I2S3_CK_133") (pintype "passive"))
    )
    (net (code "51") (name "/JTMS") (class "Default")
      (node (ref "JTAG") (pin "7") (pinfunction "TMS/SWDIO_7") (pintype "passive"))
      (node (ref "R9") (pin "2") (pintype "passive"))
      (node (ref "U1") (pin "105") (pinfunction "PA13/JTMS_SWDIO_105") (pintype "passive"))
    )
    (net (code "52") (name "/JTRST") (class "Default")
      (node (ref "JTAG") (pin "3") (pinfunction "TRST_3") (pintype "passive"))
      (node (ref "R7") (pin "2") (pintype "passive"))
      (node (ref "U1") (pin "134") (pinfunction "PB4/JNTRST/SPI3_MISO_134") (pintype "passive"))
    )
    (net (code "53") (name "/KEY0") (class "Default")
      (node (ref "KEY0") (pin "2") (pinfunction "2_2") (pintype "passive"))
      (node (ref "U1") (pin "1") (pinfunction "PE2/TRACECK/FSMC_A23_1") (pintype "passive"))
    )
    (net (code "54") (name "/KEY1") (class "Default")
      (node (ref "KEY1") (pin "2") (pinfunction "2_2") (pintype "passive"))
      (node (ref "U1") (pin "2") (pinfunction "PE3/TRACED0/FSMC_A19_2") (pintype "passive"))
    )
    (net (code "55") (name "/LCD_BL") (class "Default")
      (node (ref "LCD") (pin "23") (pinfunction "BL_23") (pintype "passive"))
      (node (ref "U1") (pin "46") (pinfunction "PB0/ADC12_IN8/TIM3_CH3/TIM8_CH2N_46") (pintype "passive"))
    )
    (net (code "56") (name "/LED1") (class "Default")
      (node (ref "DS1") (pin "K") (pinfunction "K_K") (pintype "passive"))
      (node (ref "U1") (pin "4") (pinfunction "PE5/TRACED2/FSMC_A21_4") (pintype "passive"))
    )
    (net (code "57") (name "/LED_SERIAL") (class "Default")
      (node (ref "R19") (pin "2") (pinfunction "2_2") (pintype "passive"))
      (node (ref "U1") (pin "42") (pinfunction "PA6/SPI1_MISO/TIM8_BKIN/ADC12_IN6/TIM3_CH1_42") (pintype "passive"))
    )
    (net (code "58") (name "/OLED_CS") (class "Default")
      (node (ref "P4") (pin "4") (pinfunction "4_4") (pintype "passive"))
      (node (ref "U1") (pin "122") (pinfunction "PD6/FSMC_NWAIT_122") (pintype "passive"))
    )
    (net (code "59") (name "/OLED_DC") (class "Default")
      (node (ref "P4") (pin "3") (pinfunction "3_3") (pintype "passive"))
      (node (ref "U1") (pin "117") (pinfunction "PD3/FSMC_CLK_117") (pintype "passive"))
    )
    (net (code "60") (name "/OLED_RD") (class "Default")
      (node (ref "P4") (pin "5") (pinfunction "5_5") (pintype "passive"))
      (node (ref "U1") (pin "128") (pinfunction "PG13/FSMC_A24_128") (pintype "passive"))
    )
    (net (code "61") (name "/OLED_RST") (class "Default")
      (node (ref "P4") (pin "8") (pinfunction "8_8") (pintype "passive"))
      (node (ref "U1") (pin "132") (pinfunction "PG15_132") (pintype "passive"))
    )
    (net (code "62") (name "/OLED_RW") (class "Default")
      (node (ref "P4") (pin "6") (pinfunction "6_6") (pintype "passive"))
      (node (ref "U1") (pin "129") (pinfunction "PG14/FSMC_A25_129") (pintype "passive"))
    )
    (net (code "63") (name "/OV D0") (class "Default")
      (node (ref "P4") (pin "7") (pinfunction "7_7") (pintype "passive"))
      (node (ref "U1") (pin "26") (pinfunction "PC0/ADC123_IN10_26") (pintype "passive"))
    )
    (net (code "64") (name "/OV D1") (class "Default")
      (node (ref "P4") (pin "10") (pinfunction "10_10") (pintype "passive"))
      (node (ref "U1") (pin "27") (pinfunction "PC1/ADC123_IN11_27") (pintype "passive"))
    )
    (net (code "65") (name "/OV D2") (class "Default")
      (node (ref "P4") (pin "9") (pinfunction "9_9") (pintype "passive"))
      (node (ref "U1") (pin "28") (pinfunction "PC2/ADC123_IN12_28") (pintype "passive"))
    )
    (net (code "66") (name "/OV D3") (class "Default")
      (node (ref "P4") (pin "12") (pinfunction "12_12") (pintype "passive"))
      (node (ref "U1") (pin "29") (pinfunction "PC3/ADC123_IN13_29") (pintype "passive"))
    )
    (net (code "67") (name "/OV D4") (class "Default")
      (node (ref "P4") (pin "11") (pinfunction "11_11") (pintype "passive"))
      (node (ref "U1") (pin "44") (pinfunction "PC4/ADC12_IN14_44") (pintype "passive"))
    )
    (net (code "68") (name "/OV D5") (class "Default")
      (node (ref "P4") (pin "14") (pinfunction "14_14") (pintype "passive"))
      (node (ref "U1") (pin "45") (pinfunction "PC5/ADC12_IN15_45") (pintype "passive"))
    )
    (net (code "69") (name "/OV D6") (class "Default")
      (node (ref "P4") (pin "13") (pinfunction "13_13") (pintype "passive"))
      (node (ref "U1") (pin "96") (pinfunction "PC6/I2S2_MCK/TIM8_CH1/SDIO_D6_96") (pintype "passive"))
    )
    (net (code "70") (name "/OV D7") (class "Default")
      (node (ref "P4") (pin "16") (pinfunction "16_16") (pintype "passive"))
      (node (ref "U1") (pin "97") (pinfunction "PC7/I2S3_MCK/TIM8_CH2/SDIO_D7_97") (pintype "passive"))
    )
    (net (code "71") (name "/PT PIN1") (class "Default")
      (node (ref "P2") (pin "3") (pinfunction "3_3") (pintype "passive"))
      (node (ref "R25") (pin "1") (pintype "passive"))
      (node (ref "R29") (pin "1") (pintype "passive"))
    )
    (net (code "72") (name "/PT PIN2") (class "Default")
      (node (ref "P2") (pin "2") (pinfunction "2_2") (pintype "passive"))
      (node (ref "VR2") (pin "1") (pinfunction "TOP_1") (pintype "passive"))
    )
    (net (code "73") (name "/PT100_ADC1") (class "Default")
      (node (ref "C26") (pin "2") (pintype "passive"))
      (node (ref "D4") (pin "K") (pinfunction "K_K") (pintype "passive"))
      (node (ref "R31") (pin "2") (pinfunction "2_2") (pintype "passive"))
      (node (ref "U1") (pin "40") (pinfunction "PA4/SPI1_NSS/DAC_OUT1/USART2_CK/ADC12_IN4_40") (pintype "passive"))
    )
    (net (code "74") (name "/PT100_ADC2") (class "Default")
      (node (ref "C28") (pin "2") (pintype "passive"))
      (node (ref "D11") (pin "k") (pinfunction "K_k") (pintype "passive"))
      (node (ref "R39") (pin "1") (pintype "passive"))
      (node (ref "U1") (pin "35") (pinfunction "PA1/USART2_RTS/ADC123_IN1/TIM5_CH2/TIM2_CH2_35") (pintype "passive"))
    )
    (net (code "75") (name "/PWM IN") (class "Default")
      (node (ref "R40") (pin "1") (pintype "passive"))
      (node (ref "U1") (pin "135") (pinfunction "PB5/I2C1_SMBAI/SPI3_MOSI/I2S3_SD_135") (pintype "passive"))
    )
    (net (code "76") (name "/RESET") (class "Default")
      (node (ref "C6") (pin "1") (pintype "passive"))
      (node (ref "D1") (pin "1") (pintype "passive"))
      (node (ref "JTAG") (pin "15") (pinfunction "RESET#_15") (pintype "passive"))
      (node (ref "LCD") (pin "5") (pinfunction "RST_5") (pintype "passive"))
      (node (ref "R12") (pin "1") (pintype "passive"))
      (node (ref "RESET") (pin "1") (pinfunction "1_1") (pintype "passive"))
      (node (ref "U1") (pin "25") (pinfunction "NRST_25") (pintype "passive"))
    )
    (net (code "77") (name "/RXD") (class "Default")
      (node (ref "U1") (pin "101") (pinfunction "PA9/USART1_TX/TIM1_CH2_101") (pintype "passive"))
      (node (ref "U8") (pin "3") (pinfunction "RXD_3") (pintype "passive"))
    )
    (net (code "78") (name "/RXD2") (class "Default")
      (node (ref "U1") (pin "37") (pinfunction "PA3/USART2_RX/ADC123_IN3/TIM5_CH4/TIM2_CH4_37") (pintype "passive"))
      (node (ref "U6") (pin "3") (pinfunction "UART_TXD_3") (pintype "passive"))
    )
    (net (code "79") (name "/TXD") (class "Default")
      (node (ref "U1") (pin "102") (pinfunction "PA10/USART1_RX/TIM1_CH3_102") (pintype "passive"))
      (node (ref "U8") (pin "2") (pinfunction "TXD_2") (pintype "passive"))
    )
    (net (code "80") (name "/TXD2") (class "Default")
      (node (ref "U1") (pin "36") (pinfunction "PA2/USART2_TX/ADC123_IN2/TIM5_CH3/TIM2_CH3_36") (pintype "passive"))
      (node (ref "U6") (pin "4") (pinfunction "UART_RXD_4") (pintype "passive"))
    )
    (net (code "81") (name "/T_CS") (class "Default")
      (node (ref "LCD") (pin "33") (pinfunction "T_CS_33") (pintype "passive"))
      (node (ref "U1") (pin "49") (pinfunction "PF11/FSMC_NIOS16_49") (pintype "passive"))
    )
    (net (code "82") (name "/T_MOSI") (class "Default")
      (node (ref "LCD") (pin "30") (pinfunction "MOSI_30") (pintype "passive"))
      (node (ref "U1") (pin "21") (pinfunction "PF9/ADC3_IN7/FSMC_CD_21") (pintype "passive"))
    )
    (net (code "83") (name "/T_PEN") (class "Default")
      (node (ref "LCD") (pin "31") (pinfunction "T_PEN_31") (pintype "passive"))
      (node (ref "U1") (pin "22") (pinfunction "PF10/ADC3_IN8/FSMC_INTR_22") (pintype "passive"))
    )
    (net (code "84") (name "/T_SCK") (class "Default")
      (node (ref "LCD") (pin "34") (pinfunction "CLK_34") (pintype "passive"))
      (node (ref "U1") (pin "47") (pinfunction "PB1/ADC12_IN9/TIM3_CH4/TIM8_CH3N_47") (pintype "passive"))
    )
    (net (code "85") (name "/VREF+") (class "Default")
      (node (ref "C53") (pin "2") (pintype "passive"))
      (node (ref "U1") (pin "32") (pinfunction "Vref+_32") (pintype "passive"))
      (node (ref "p7") (pin "2") (pinfunction "OUT_2") (pintype "passive"))
    )
    (net (code "86") (name "/WIFI_LINK") (class "Default")
      (node (ref "R17") (pin "2") (pinfunction "2_2") (pintype "passive"))
      (node (ref "U1") (pin "100") (pinfunction "PA8/USART1_CK/TIM1_CH1/MCO_100") (pintype "passive"))
      (node (ref "U6") (pin "8") (pinfunction "nLink_8") (pintype "passive"))
    )
    (net (code "87") (name "/WIFI_READY") (class "Default")
      (node (ref "R18") (pin "2") (pinfunction "2_2") (pintype "passive"))
      (node (ref "U1") (pin "41") (pinfunction "PA5/SPI1_SCK/DAC_OUT2/ADC12_IN5_41") (pintype "passive"))
      (node (ref "U6") (pin "9") (pinfunction "nReady_9") (pintype "passive"))
    )
    (net (code "88") (name "/WIFI_RESET") (class "Default")
      (node (ref "U1") (pin "43") (pinfunction "PA7/SPI1_MOSI/TIM8_CH1N/ADC12_IN7/TIM3_CH2_43") (pintype "passive"))
      (node (ref "U6") (pin "7") (pinfunction "RESET_7") (pintype "passive"))
    )
    (net (code "89") (name "24V") (class "Default")
      (node (ref "C17") (pin "A") (pinfunction "A_A") (pintype "passive"))
      (node (ref "C18") (pin "2") (pinfunction "2_2") (pintype "passive"))
      (node (ref "C19") (pin "A") (pinfunction "A_A") (pintype "passive"))
      (node (ref "C20") (pin "2") (pinfunction "2_2") (pintype "passive"))
      (node (ref "C29") (pin "A") (pinfunction "A_A") (pintype "passive"))
      (node (ref "C30") (pin "1") (pintype "passive"))
      (node (ref "K2") (pin "1") (pinfunction "1_1") (pintype "passive"))
      (node (ref "LM2") (pin "1") (pinfunction "VI_1") (pintype "passive"))
      (node (ref "P10") (pin "1") (pinfunction "1_1") (pintype "passive"))
      (node (ref "P11") (pin "2") (pinfunction "2_2") (pintype "passive"))
      (node (ref "Q6") (pin "1") (pinfunction "E_1") (pintype "passive"))
    )
    (net (code "90") (name "AGND") (class "Default")
      (node (ref "C25") (pin "2") (pintype "passive"))
      (node (ref "C26") (pin "1") (pintype "passive"))
      (node (ref "C27") (pin "2") (pintype "passive"))
      (node (ref "C28") (pin "1") (pintype "passive"))
      (node (ref "C48") (pin "1") (pintype "passive"))
      (node (ref "C49") (pin "1") (pintype "passive"))
      (node (ref "C50") (pin "1") (pintype "passive"))
      (node (ref "C51") (pin "1") (pintype "passive"))
      (node (ref "C52") (pin "1") (pintype "passive"))
      (node (ref "C53") (pin "1") (pintype "passive"))
      (node (ref "C7") (pin "1") (pintype "passive"))
      (node (ref "C8") (pin "2") (pintype "passive"))
      (node (ref "D11") (pin "A") (pinfunction "1_A") (pintype "passive"))
      (node (ref "D4") (pin "A") (pinfunction "A_A") (pintype "passive"))
      (node (ref "P2") (pin "1") (pinfunction "1_1") (pintype "passive"))
      (node (ref "R27") (pin "1") (pintype "passive"))
      (node (ref "R33") (pin "1") (pintype "passive"))
      (node (ref "R34") (pin "2") (pintype "passive"))
      (node (ref "R37") (pin "1") (pintype "passive"))
      (node (ref "U1") (pin "30") (pinfunction "VSSA_30") (pintype "passive"))
      (node (ref "U1") (pin "31") (pinfunction "Vref-_31") (pintype "passive"))
      (node (ref "U2") (pin "4") (pinfunction "VCC-_4") (pintype "passive"))
      (node (ref "U3") (pin "11") (pinfunction "GND_11") (pintype "passive"))
      (node (ref "p5") (pin "3") (pinfunction "GND_3") (pintype "passive"))
      (node (ref "p6") (pin "3") (pinfunction "GND_3") (pintype "passive"))
      (node (ref "p7") (pin "3") (pinfunction "GND_3") (pintype "passive"))
    )
    (net (code "91") (name "GND") (class "Default")
      (node (ref "BAT1") (pin "2") (pinfunction "GND_2") (pintype "passive"))
      (node (ref "C1") (pin "1") (pintype "passive"))
      (node (ref "C10") (pin "1") (pintype "passive"))
      (node (ref "C11") (pin "1") (pintype "passive"))
      (node (ref "C12") (pin "1") (pintype "passive"))
      (node (ref "C13") (pin "1") (pintype "passive"))
      (node (ref "C14") (pin "1") (pinfunction "1_1") (pintype "passive"))
      (node (ref "C15") (pin "K") (pinfunction "K_K") (pintype "passive"))
      (node (ref "C16") (pin "K") (pinfunction "K_K") (pintype "passive"))
      (node (ref "C17") (pin "K") (pinfunction "K_K") (pintype "passive"))
      (node (ref "C18") (pin "1") (pinfunction "1_1") (pintype "passive"))
      (node (ref "C19") (pin "K") (pinfunction "K_K") (pintype "passive"))
      (node (ref "C2") (pin "1") (pintype "passive"))
      (node (ref "C20") (pin "1") (pinfunction "1_1") (pintype "passive"))
      (node (ref "C21") (pin "2") (pintype "passive"))
      (node (ref "C22") (pin "2") (pintype "passive"))
      (node (ref "C23") (pin "1") (pintype "passive"))
      (node (ref "C24") (pin "1") (pintype "passive"))
      (node (ref "C29") (pin "K") (pinfunction "K_K") (pintype "passive"))
      (node (ref "C3") (pin "2") (pintype "passive"))
      (node (ref "C30") (pin "2") (pintype "passive"))
      (node (ref "C31") (pin "K") (pinfunction "K_K") (pintype "passive"))
      (node (ref "C32") (pin "2") (pinfunction "2_2") (pintype "passive"))
      (node (ref "C34") (pin "1") (pintype "passive"))
      (node (ref "C35") (pin "1") (pintype "passive"))
      (node (ref "C36") (pin "1") (pintype "passive"))
      (node (ref "C37") (pin "1") (pintype "passive"))
      (node (ref "C38") (pin "1") (pintype "passive"))
      (node (ref "C39") (pin "1") (pintype "passive"))
      (node (ref "C4") (pin "1") (pintype "passive"))
      (node (ref "C40") (pin "1") (pintype "passive"))
      (node (ref "C41") (pin "1") (pintype "passive"))
      (node (ref "C42") (pin "1") (pintype "passive"))
      (node (ref "C43") (pin "1") (pintype "passive"))
      (node (ref "C44") (pin "1") (pintype "passive"))
      (node (ref "C45") (pin "1") (pinfunction "1_1") (pintype "passive"))
      (node (ref "C5") (pin "1") (pintype "passive"))
      (node (ref "C6") (pin "2") (pintype "passive"))
      (node (ref "C9") (pin "1") (pintype "passive"))
      (node (ref "D12") (pin "A") (pinfunction "A_A") (pintype "passive"))
      (node (ref "DS2") (pin "K") (pinfunction "K_K") (pintype "passive"))
      (node (ref "JTAG") (pin "10") (pinfunction "GND_10") (pintype "passive"))
      (node (ref "JTAG") (pin "12") (pinfunction "GND_12") (pintype "passive"))
      (node (ref "JTAG") (pin "14") (pinfunction "GND_14") (pintype "passive"))
      (node (ref "JTAG") (pin "16") (pinfunction "GND_16") (pintype "passive"))
      (node (ref "JTAG") (pin "18") (pinfunction "GND_18") (pintype "passive"))
      (node (ref "JTAG") (pin "20") (pinfunction "GND_20") (pintype "passive"))
      (node (ref "JTAG") (pin "4") (pinfunction "GND_4") (pintype "passive"))
      (node (ref "JTAG") (pin "6") (pinfunction "GND_6") (pintype "passive"))
      (node (ref "JTAG") (pin "8") (pinfunction "GND_8") (pintype "passive"))
      (node (ref "JUMP1") (pin "2") (pinfunction "2_2") (pintype "passive"))
      (node (ref "KEY0") (pin "1") (pinfunction "1_1") (pintype "passive"))
      (node (ref "KEY1") (pin "1") (pinfunction "1_1") (pintype "passive"))
      (node (ref "LCD") (pin "22") (pinfunction "GND_22") (pintype "passive"))
      (node (ref "LCD") (pin "26") (pinfunction "GND_26") (pintype "passive"))
      (node (ref "LCD") (pin "27") (pinfunction "GND_27") (pintype "passive"))
      (node (ref "LM2") (pin "3") (pinfunction "GND_3") (pintype "passive"))
      (node (ref "LM2") (pin "5") (pinfunction "EN_5") (pintype "passive"))
      (node (ref "P11") (pin "1") (pinfunction "1_1") (pintype "passive"))
      (node (ref "P4") (pin "1") (pinfunction "1_1") (pintype "passive"))
      (node (ref "Q5") (pin "1") (pinfunction "E_1") (pintype "passive"))
      (node (ref "Q7") (pin "1") (pinfunction "E_1") (pintype "passive"))
      (node (ref "Q8") (pin "3") (pinfunction "S_3") (pintype "passive"))
      (node (ref "R10") (pin "1") (pintype "passive"))
      (node (ref "R16") (pin "2") (pinfunction "2_2") (pintype "passive"))
      (node (ref "R33") (pin "2") (pintype "passive"))
      (node (ref "R44") (pin "1") (pintype "passive"))
      (node (ref "R47") (pin "1") (pintype "passive"))
      (node (ref "R5") (pin "2") (pintype "passive"))
      (node (ref "R6") (pin "2") (pintype "passive"))
      (node (ref "RESET") (pin "2") (pinfunction "2_2") (pintype "passive"))
      (node (ref "U1") (pin "107") (pinfunction "VSS_107") (pintype "passive"))
      (node (ref "U1") (pin "120") (pinfunction "VSS_120") (pintype "passive"))
      (node (ref "U1") (pin "130") (pinfunction "VSS_130") (pintype "passive"))
      (node (ref "U1") (pin "143") (pinfunction "VSS_143") (pintype "passive"))
      (node (ref "U1") (pin "16") (pinfunction "VSS_16") (pintype "passive"))
      (node (ref "U1") (pin "38") (pinfunction "VSS_38") (pintype "passive"))
      (node (ref "U1") (pin "51") (pinfunction "VSS_51") (pintype "passive"))
      (node (ref "U1") (pin "61") (pinfunction "VSS_61") (pintype "passive"))
      (node (ref "U1") (pin "71") (pinfunction "VSS_71") (pintype "passive"))
      (node (ref "U1") (pin "83") (pinfunction "VSS_83") (pintype "passive"))
      (node (ref "U1") (pin "94") (pinfunction "VSS_94") (pintype "passive"))
      (node (ref "U4") (pin "12") (pinfunction "GND_12") (pintype "passive"))
      (node (ref "U4") (pin "34") (pinfunction "GND_34") (pintype "passive"))
      (node (ref "U5") (pin "1") (pinfunction "GND_1") (pintype "passive"))
      (node (ref "U6") (pin "1") (pinfunction "GND_1") (pintype "passive"))
      (node (ref "U7") (pin "1") (pinfunction "A0_1") (pintype "passive"))
      (node (ref "U7") (pin "2") (pinfunction "A1_2") (pintype "passive"))
      (node (ref "U7") (pin "3") (pinfunction "A2_3") (pintype "passive"))
      (node (ref "U7") (pin "4") (pinfunction "GND_4") (pintype "passive"))
      (node (ref "U7") (pin "7") (pinfunction "WP_7") (pintype "passive"))
      (node (ref "U8") (pin "1") (pinfunction "GND_1") (pintype "passive"))
      (node (ref "USB_232") (pin "5") (pinfunction "GND_5") (pintype "passive"))
    )
    (net (code "92") (name "Net-(BAT1-VCC)") (class "Default")
      (node (ref "BAT1") (pin "1") (pinfunction "VCC_1") (pintype "passive"))
      (node (ref "C11") (pin "2") (pintype "passive"))
      (node (ref "D3") (pin "1") (pintype "passive"))
    )
    (net (code "93") (name "Net-(D5-PadK)") (class "Default")
      (node (ref "D5") (pin "K") (pinfunction "K_K") (pintype "passive"))
      (node (ref "R16") (pin "1") (pinfunction "1_1") (pintype "passive"))
    )
    (net (code "94") (name "Net-(D6-PadK)") (class "Default")
      (node (ref "D6") (pin "K") (pinfunction "K_K") (pintype "passive"))
      (node (ref "R17") (pin "1") (pinfunction "1_1") (pintype "passive"))
    )
    (net (code "95") (name "Net-(D7-PadK)") (class "Default")
      (node (ref "D7") (pin "K") (pinfunction "K_K") (pintype "passive"))
      (node (ref "R18") (pin "1") (pinfunction "1_1") (pintype "passive"))
    )
    (net (code "96") (name "Net-(D8-PadK)") (class "Default")
      (node (ref "D8") (pin "K") (pinfunction "K_K") (pintype "passive"))
      (node (ref "R19") (pin "1") (pinfunction "1_1") (pintype "passive"))
    )
    (net (code "97") (name "Net-(DS1-PadA)") (class "Default")
      (node (ref "DS1") (pin "A") (pinfunction "A_A") (pintype "passive"))
      (node (ref "R23") (pin "1") (pintype "passive"))
    )
    (net (code "98") (name "Net-(DS2-PadA)") (class "Default")
      (node (ref "DS2") (pin "A") (pinfunction "A_A") (pintype "passive"))
      (node (ref "R24") (pin "1") (pintype "passive"))
    )
    (net (code "99") (name "Net-(LM2-VO)") (class "Default")
      (node (ref "D12") (pin "K") (pinfunction "K_K") (pintype "passive"))
      (node (ref "L1") (pin "2") (pinfunction "2_2") (pintype "passive"))
      (node (ref "LM2") (pin "2") (pinfunction "VO_2") (pintype "passive"))
    )
    (net (code "100") (name "Net-(Q1-B)") (class "Default")
      (node (ref "Q1") (pin "2") (pinfunction "B_2") (pintype "passive"))
      (node (ref "R2") (pin "1") (pintype "passive"))
    )
    (net (code "101") (name "Net-(Q1-C)") (class "Default")
      (node (ref "D1") (pin "2") (pintype "passive"))
      (node (ref "Q1") (pin "3") (pinfunction "C_3") (pintype "passive"))
      (node (ref "R1") (pin "1") (pintype "passive"))
    )
    (net (code "102") (name "Net-(Q1-E)") (class "Default")
      (node (ref "Q1") (pin "1") (pinfunction "E_1") (pintype "passive"))
      (node (ref "R3") (pin "2") (pintype "passive"))
      (node (ref "U8") (pin "14") (pinfunction "RTS#_14") (pintype "passive"))
    )
    (net (code "103") (name "Net-(Q2-B)") (class "Default")
      (node (ref "Q2") (pin "2") (pinfunction "B_2") (pintype "passive"))
      (node (ref "R3") (pin "1") (pintype "passive"))
    )
    (net (code "104") (name "Net-(Q2-C)") (class "Default")
      (node (ref "Q2") (pin "3") (pinfunction "C_3") (pintype "passive"))
      (node (ref "R4") (pin "2") (pintype "passive"))
    )
    (net (code "105") (name "Net-(Q3-B)") (class "Default")
      (node (ref "Q3") (pin "2") (pinfunction "B_2") (pintype "passive"))
      (node (ref "Q4") (pin "2") (pinfunction "B_2") (pintype "passive"))
      (node (ref "Q7") (pin "3") (pinfunction "C_3") (pintype "passive"))
      (node (ref "R43") (pin "1") (pintype "passive"))
      (node (ref "R44") (pin "2") (pintype "passive"))
    )
    (net (code "106") (name "Net-(Q3-C)") (class "Default")
      (node (ref "Q3") (pin "3") (pinfunction "C_3") (pintype "passive"))
      (node (ref "Q6") (pin "2") (pinfunction "B_2") (pintype "passive"))
    )
    (net (code "107") (name "Net-(Q3-E)") (class "Default")
      (node (ref "Q3") (pin "1") (pinfunction "E_1") (pintype "passive"))
      (node (ref "Q4") (pin "1") (pinfunction "E_1") (pintype "passive"))
      (node (ref "R40") (pin "2") (pintype "passive"))
    )
    (net (code "108") (name "Net-(Q4-C)") (class "Default")
      (node (ref "Q4") (pin "3") (pinfunction "C_3") (pintype "passive"))
      (node (ref "Q5") (pin "2") (pinfunction "B_2") (pintype "passive"))
    )
    (net (code "109") (name "Net-(Q5-C)") (class "Default")
      (node (ref "C47") (pin "1") (pintype "passive"))
      (node (ref "Q5") (pin "3") (pinfunction "C_3") (pintype "passive"))
      (node (ref "Q6") (pin "3") (pinfunction "C_3") (pintype "passive"))
      (node (ref "R45") (pin "2") (pintype "passive"))
    )
    (net (code "110") (name "Net-(Q7-B)") (class "Default")
      (node (ref "Q7") (pin "2") (pinfunction "B_2") (pintype "passive"))
      (node (ref "R46") (pin "1") (pintype "passive"))
      (node (ref "R47") (pin "2") (pintype "passive"))
    )
    (net (code "111") (name "Net-(Q8-D)") (class "Default")
      (node (ref "P10") (pin "2") (pinfunction "2_2") (pintype "passive"))
      (node (ref "Q8") (pin "2") (pinfunction "D_2") (pintype "passive"))
    )
    (net (code "112") (name "Net-(Q8-G)") (class "Default")
      (node (ref "C47") (pin "2") (pintype "passive"))
      (node (ref "Q8") (pin "1") (pinfunction "G_1") (pintype "passive"))
      (node (ref "R45") (pin "1") (pintype "passive"))
      (node (ref "R46") (pin "2") (pintype "passive"))
    )
    (net (code "113") (name "Net-(U1-OSC_IN)") (class "Default")
      (node (ref "C10") (pin "2") (pintype "passive"))
      (node (ref "R14") (pin "2") (pintype "passive"))
      (node (ref "U1") (pin "23") (pinfunction "OSC_IN_23") (pintype "passive"))
      (node (ref "Y1") (pin "1") (pinfunction "OSC1_1") (pintype "passive"))
    )
    (net (code "114") (name "Net-(U1-OSC_OUT)") (class "Default")
      (node (ref "C9") (pin "2") (pintype "passive"))
      (node (ref "R14") (pin "1") (pintype "passive"))
      (node (ref "U1") (pin "24") (pinfunction "OSC_OUT_24") (pintype "passive"))
      (node (ref "Y1") (pin "2") (pinfunction "OSC2_2") (pintype "passive"))
    )
    (net (code "115") (name "Net-(U1-PC14-OSC32_IN)") (class "Default")
      (node (ref "C23") (pin "2") (pintype "passive"))
      (node (ref "U1") (pin "8") (pinfunction "PC14-OSC32_IN_8") (pintype "passive"))
      (node (ref "Y2") (pin "2") (pinfunction "OSC2_2") (pintype "passive"))
    )
    (net (code "116") (name "Net-(U1-PC15-OSC32_OUT)") (class "Default")
      (node (ref "C24") (pin "2") (pintype "passive"))
      (node (ref "U1") (pin "9") (pinfunction "PC15-OSC32_OUT_9") (pintype "passive"))
      (node (ref "Y2") (pin "1") (pinfunction "OSC1_1") (pintype "passive"))
    )
    (net (code "117") (name "Net-(U1-VBAT)") (class "Default")
      (node (ref "D2") (pin "2") (pintype "passive"))
      (node (ref "D3") (pin "2") (pintype "passive"))
      (node (ref "U1") (pin "6") (pinfunction "VBAT_6") (pintype "passive"))
    )
    (net (code "118") (name "Net-(U2A-1_out)") (class "Default")
      (node (ref "P3") (pin "2") (pinfunction "2_2") (pintype "passive"))
      (node (ref "R36") (pin "2") (pintype "passive"))
      (node (ref "U2") (pin "1") (pinfunction "1_out_1") (pintype "passive"))
    )
    (net (code "119") (name "Net-(U2A-1in+)") (class "Default")
      (node (ref "C51") (pin "2") (pintype "passive"))
      (node (ref "U2") (pin "3") (pinfunction "1in+_3") (pintype "passive"))
      (node (ref "p6") (pin "2") (pinfunction "OUT_2") (pintype "passive"))
    )
    (net (code "120") (name "Net-(U2A-1in-)") (class "Default")
      (node (ref "P3") (pin "1") (pinfunction "1_1") (pintype "passive"))
      (node (ref "R34") (pin "1") (pintype "passive"))
      (node (ref "R35") (pin "1") (pintype "passive"))
      (node (ref "U2") (pin "2") (pinfunction "1in-_2") (pintype "passive"))
    )
    (net (code "121") (name "Net-(U2B-2_out)") (class "Default")
      (node (ref "R38") (pin "1") (pintype "passive"))
      (node (ref "R39") (pin "2") (pintype "passive"))
      (node (ref "U2") (pin "7") (pinfunction "2_out_7") (pintype "passive"))
    )
    (net (code "122") (name "Net-(U2B-2in+)") (class "Default")
      (node (ref "R36") (pin "1") (pintype "passive"))
      (node (ref "R37") (pin "2") (pintype "passive"))
      (node (ref "U2") (pin "5") (pinfunction "2in+_5") (pintype "passive"))
    )
    (net (code "123") (name "Net-(U2B-2in-)") (class "Default")
      (node (ref "R35") (pin "2") (pintype "passive"))
      (node (ref "R38") (pin "2") (pintype "passive"))
      (node (ref "U2") (pin "6") (pinfunction "2in-_6") (pintype "passive"))
    )
    (net (code "124") (name "Net-(U3A-1_out)") (class "Default")
      (node (ref "R31") (pin "1") (pinfunction "1_1") (pintype "passive"))
      (node (ref "R32") (pin "2") (pintype "passive"))
      (node (ref "U3") (pin "1") (pinfunction "1_out_1") (pintype "passive"))
    )
    (net (code "125") (name "Net-(U3A-1in+)") (class "Default")
      (node (ref "R25") (pin "2") (pintype "passive"))
      (node (ref "R27") (pin "2") (pintype "passive"))
      (node (ref "U3") (pin "3") (pinfunction "1in+_3") (pintype "passive"))
    )
    (net (code "126") (name "Net-(U3A-1in-)") (class "Default")
      (node (ref "R26") (pin "2") (pintype "passive"))
      (node (ref "R32") (pin "1") (pintype "passive"))
      (node (ref "U3") (pin "2") (pinfunction "1in-_2") (pintype "passive"))
    )
    (net (code "127") (name "Net-(U6-nReload)") (class "Default")
      (node (ref "JUMP1") (pin "1") (pinfunction "1_1") (pintype "passive"))
      (node (ref "R20") (pin "1") (pinfunction "1_1") (pintype "passive"))
      (node (ref "U6") (pin "10") (pinfunction "nReload_10") (pintype "passive"))
    )
    (net (code "128") (name "Net-(U8-DTR#)") (class "Default")
      (node (ref "R2") (pin "2") (pintype "passive"))
      (node (ref "U8") (pin "13") (pinfunction "DTR#_13") (pintype "passive"))
    )
    (net (code "129") (name "Net-(U8-V3)") (class "Default")
      (node (ref "C3") (pin "1") (pintype "passive"))
      (node (ref "U8") (pin "4") (pinfunction "V3_4") (pintype "passive"))
    )
    (net (code "130") (name "Net-(U8-XI)") (class "Default")
      (node (ref "C5") (pin "2") (pintype "passive"))
      (node (ref "U8") (pin "7") (pinfunction "XI_7") (pintype "passive"))
      (node (ref "Y3") (pin "1") (pinfunction "OSC1_1") (pintype "passive"))
    )
    (net (code "131") (name "Net-(U8-XO)") (class "Default")
      (node (ref "C4") (pin "2") (pintype "passive"))
      (node (ref "U8") (pin "8") (pinfunction "XO_8") (pintype "passive"))
      (node (ref "Y3") (pin "2") (pinfunction "OSC2_2") (pintype "passive"))
    )
    (net (code "132") (name "Net-(VR2-BOT)") (class "Default")
      (node (ref "R26") (pin "1") (pintype "passive"))
      (node (ref "R28") (pin "1") (pintype "passive"))
      (node (ref "VR2") (pin "2") (pinfunction "BOT_2") (pintype "passive"))
      (node (ref "VR2") (pin "3") (pinfunction "TAP_3") (pintype "passive"))
    )
    (net (code "133") (name "Net-(p5-OUT)") (class "Default")
      (node (ref "C49") (pin "2") (pintype "passive"))
      (node (ref "R28") (pin "2") (pintype "passive"))
      (node (ref "R29") (pin "2") (pintype "passive"))
      (node (ref "p5") (pin "2") (pinfunction "OUT_2") (pintype "passive"))
    )
    (net (code "134") (name "VCC3.3") (class "Default")
      (node (ref "C12") (pin "2") (pintype "passive"))
      (node (ref "C13") (pin "2") (pintype "passive"))
      (node (ref "C16") (pin "A") (pinfunction "A_A") (pintype "passive"))
      (node (ref "C21") (pin "1") (pintype "passive"))
      (node (ref "C34") (pin "2") (pintype "passive"))
      (node (ref "C35") (pin "2") (pintype "passive"))
      (node (ref "C36") (pin "2") (pintype "passive"))
      (node (ref "C37") (pin "2") (pintype "passive"))
      (node (ref "C38") (pin "2") (pintype "passive"))
      (node (ref "C39") (pin "2") (pintype "passive"))
      (node (ref "C40") (pin "2") (pintype "passive"))
      (node (ref "C41") (pin "2") (pintype "passive"))
      (node (ref "C42") (pin "2") (pintype "passive"))
      (node (ref "C43") (pin "2") (pintype "passive"))
      (node (ref "C44") (pin "2") (pintype "passive"))
      (node (ref "C45") (pin "2") (pinfunction "2_2") (pintype "passive"))
      (node (ref "C48") (pin "2") (pintype "passive"))
      (node (ref "C50") (pin "2") (pintype "passive"))
      (node (ref "C52") (pin "2") (pintype "passive"))
      (node (ref "D2") (pin "1") (pintype "passive"))
      (node (ref "D5") (pin "A") (pinfunction "A_A") (pintype "passive"))
      (node (ref "D6") (pin "A") (pinfunction "A_A") (pintype "passive"))
      (node (ref "D7") (pin "A") (pinfunction "A_A") (pintype "passive"))
      (node (ref "D8") (pin "A") (pinfunction "A_A") (pintype "passive"))
      (node (ref "JTAG") (pin "1") (pinfunction "VDD_1") (pintype "passive"))
      (node (ref "JTAG") (pin "2") (pinfunction "VDD_2") (pintype "passive"))
      (node (ref "LCD") (pin "24") (pinfunction "VDD3.3_24") (pintype "passive"))
      (node (ref "LCD") (pin "25") (pinfunction "VDD3.3_25") (pintype "passive"))
      (node (ref "P4") (pin "2") (pinfunction "2_2") (pintype "passive"))
      (node (ref "Q2") (pin "1") (pinfunction "E_1") (pintype "passive"))
      (node (ref "R1") (pin "2") (pintype "passive"))
      (node (ref "R11") (pin "1") (pintype "passive"))
      (node (ref "R12") (pin "2") (pintype "passive"))
      (node (ref "R13") (pin "2") (pintype "passive"))
      (node (ref "R15") (pin "2") (pintype "passive"))
      (node (ref "R20") (pin "2") (pinfunction "2_2") (pintype "passive"))
      (node (ref "R23") (pin "2") (pintype "passive"))
      (node (ref "R24") (pin "2") (pintype "passive"))
      (node (ref "R41") (pin "2") (pintype "passive"))
      (node (ref "R42") (pin "2") (pintype "passive"))
      (node (ref "R43") (pin "2") (pintype "passive"))
      (node (ref "R7") (pin "1") (pintype "passive"))
      (node (ref "R8") (pin "1") (pintype "passive"))
      (node (ref "R9") (pin "1") (pintype "passive"))
      (node (ref "U1") (pin "108") (pinfunction "VDD_108") (pintype "passive"))
      (node (ref "U1") (pin "121") (pinfunction "VDD_121") (pintype "passive"))
      (node (ref "U1") (pin "131") (pinfunction "VDD_131") (pintype "passive"))
      (node (ref "U1") (pin "144") (pinfunction "VDD_144") (pintype "passive"))
      (node (ref "U1") (pin "17") (pinfunction "VDD_17") (pintype "passive"))
      (node (ref "U1") (pin "39") (pinfunction "VDD_39") (pintype "passive"))
      (node (ref "U1") (pin "52") (pinfunction "VDD_52") (pintype "passive"))
      (node (ref "U1") (pin "62") (pinfunction "VDD_62") (pintype "passive"))
      (node (ref "U1") (pin "72") (pinfunction "VDD_72") (pintype "passive"))
      (node (ref "U1") (pin "84") (pinfunction "VDD_84") (pintype "passive"))
      (node (ref "U1") (pin "95") (pinfunction "VDD_95") (pintype "passive"))
      (node (ref "U4") (pin "11") (pinfunction "VDD_11") (pintype "passive"))
      (node (ref "U4") (pin "33") (pinfunction "VDD_33") (pintype "passive"))
      (node (ref "U5") (pin "2") (pinfunction "VOUT_2") (pintype "passive"))
      (node (ref "U6") (pin "2") (pinfunction "3.3V_2") (pintype "passive"))
      (node (ref "U7") (pin "8") (pinfunction "VCC1_8") (pintype "passive"))
      (node (ref "p5") (pin "1") (pinfunction "IN_1") (pintype "passive"))
      (node (ref "p6") (pin "1") (pinfunction "IN_1") (pintype "passive"))
      (node (ref "p7") (pin "1") (pinfunction "IN_1") (pintype "passive"))
    )
    (net (code "135") (name "VCC5") (class "Default")
      (node (ref "C1") (pin "2") (pintype "passive"))
      (node (ref "C14") (pin "2") (pinfunction "2_2") (pintype "passive"))
      (node (ref "C15") (pin "A") (pinfunction "A_A") (pintype "passive"))
      (node (ref "C2") (pin "2") (pintype "passive"))
      (node (ref "C22") (pin "1") (pintype "passive"))
      (node (ref "C25") (pin "1") (pintype "passive"))
      (node (ref "C27") (pin "1") (pintype "passive"))
      (node (ref "C31") (pin "A") (pinfunction "A_A") (pintype "passive"))
      (node (ref "C32") (pin "1") (pinfunction "1_1") (pintype "passive"))
      (node (ref "K2") (pin "2") (pinfunction "2_2") (pintype "passive"))
      (node (ref "L1") (pin "1") (pinfunction "1_1") (pintype "passive"))
      (node (ref "LCD") (pin "28") (pinfunction "BL_VDD_28") (pintype "passive"))
      (node (ref "LM2") (pin "4") (pinfunction "FB_4") (pintype "passive"))
      (node (ref "U2") (pin "8") (pinfunction "VCC+_8") (pintype "passive"))
      (node (ref "U3") (pin "4") (pinfunction "VCC_4") (pintype "passive"))
      (node (ref "U5") (pin "3") (pinfunction "VIN_3") (pintype "passive"))
      (node (ref "U8") (pin "16") (pinfunction "VCC_16") (pintype "passive"))
      (node (ref "USB_232") (pin "1") (pinfunction "VCC_1") (pintype "passive"))
    )
    (net (code "136") (name "VDDA") (class "Default")
      (node (ref "C7") (pin "2") (pintype "passive"))
      (node (ref "C8") (pin "1") (pintype "passive"))
      (node (ref "R13") (pin "1") (pintype "passive"))
      (node (ref "U1") (pin "33") (pinfunction "VDDA_33") (pintype "passive"))
    )
    (net (code "137") (name "unconnected-(JTAG-NC-Pad11)") (class "Default")
      (node (ref "JTAG") (pin "11") (pinfunction "NC_11") (pintype "passive"))
    )
    (net (code "138") (name "unconnected-(JTAG-NC-Pad17)") (class "Default")
      (node (ref "JTAG") (pin "17") (pinfunction "NC_17") (pintype "passive"))
    )
    (net (code "139") (name "unconnected-(JTAG-NC-Pad19)") (class "Default")
      (node (ref "JTAG") (pin "19") (pinfunction "NC_19") (pintype "passive"))
    )
    (net (code "140") (name "unconnected-(LCD-MO-Pad32)") (class "Default")
      (node (ref "LCD") (pin "32") (pinfunction "MO_32") (pintype "passive"))
    )
    (net (code "141") (name "unconnected-(P4-Pad15)") (class "Default")
      (node (ref "P4") (pin "15") (pinfunction "15_15") (pintype "passive"))
    )
    (net (code "142") (name "unconnected-(U1-NC-Pad106)") (class "Default")
      (node (ref "U1") (pin "106") (pinfunction "NC_106") (pintype "passive"))
    )
    (net (code "143") (name "unconnected-(U1-PA0-WKUP{slash}USART2_CTS{slash}ADC123_IN0{slash}TIM5_CH1{slash}TIM2_CH1_ETR{slash}TIM8_ETR-Pad34)") (class "Default")
      (node (ref "U1") (pin "34") (pinfunction "PA0-WKUP/USART2_CTS/ADC123_IN0/TIM5_CH1/TIM2_CH1_ETR/TIM8_ETR_34") (pintype "passive"))
    )
    (net (code "144") (name "unconnected-(U1-PA11{slash}USART1_CTS{slash}CAN_RX{slash}TIM1_CH4{slash}USBDM-Pad103)") (class "Default")
      (node (ref "U1") (pin "103") (pinfunction "PA11/USART1_CTS/CAN_RX/TIM1_CH4/USBDM_103") (pintype "passive"))
    )
    (net (code "145") (name "unconnected-(U1-PA12{slash}USART1_RTS{slash}CAN_TX{slash}TIM1_ETR{slash}USBDP-Pad104)") (class "Default")
      (node (ref "U1") (pin "104") (pinfunction "PA12/USART1_RTS/CAN_TX/TIM1_ETR/USBDP_104") (pintype "passive"))
    )
    (net (code "146") (name "unconnected-(U1-PB8{slash}TIM4_CH3{slash}SDIO_D4-Pad139)") (class "Default")
      (node (ref "U1") (pin "139") (pinfunction "PB8/TIM4_CH3/SDIO_D4_139") (pintype "passive"))
    )
    (net (code "147") (name "unconnected-(U1-PB9{slash}TIM4_CH4{slash}SDIO_D5-Pad140)") (class "Default")
      (node (ref "U1") (pin "140") (pinfunction "PB9/TIM4_CH4/SDIO_D5_140") (pintype "passive"))
    )
    (net (code "148") (name "unconnected-(U1-PB10{slash}I2C2_SCL{slash}USART3_TX-Pad69)") (class "Default")
      (node (ref "U1") (pin "69") (pinfunction "PB10/I2C2_SCL/USART3_TX_69") (pintype "passive"))
    )
    (net (code "149") (name "unconnected-(U1-PB11{slash}I2C2_SDA{slash}USART3_RX-Pad70)") (class "Default")
      (node (ref "U1") (pin "70") (pinfunction "PB11/I2C2_SDA/USART3_RX_70") (pintype "passive"))
    )
    (net (code "150") (name "unconnected-(U1-PB12{slash}SPI2_NSS{slash}I2S2_WS{slash}I2C2_SMBAI{slash}USART3_CK{slash}TIM1BKIN-Pad73)") (class "Default")
      (node (ref "U1") (pin "73") (pinfunction "PB12/SPI2_NSS/I2S2_WS/I2C2_SMBAI/USART3_CK/TIM1BKIN_73") (pintype "passive"))
    )
    (net (code "151") (name "unconnected-(U1-PB13{slash}SPI2_SCK{slash}I2S2_CK{slash}USART3_CTS{slash}TIM1_CH1N-Pad74)") (class "Default")
      (node (ref "U1") (pin "74") (pinfunction "PB13/SPI2_SCK/I2S2_CK/USART3_CTS/TIM1_CH1N_74") (pintype "passive"))
    )
    (net (code "152") (name "unconnected-(U1-PB14{slash}SPI2_MISO{slash}USART3_RTS{slash}TIM1_CH2N-Pad75)") (class "Default")
      (node (ref "U1") (pin "75") (pinfunction "PB14/SPI2_MISO/USART3_RTS/TIM1_CH2N_75") (pintype "passive"))
    )
    (net (code "153") (name "unconnected-(U1-PB15{slash}SPI2_MOSI{slash}I2S2_SD{slash}TIM1_CH3N-Pad76)") (class "Default")
      (node (ref "U1") (pin "76") (pinfunction "PB15/SPI2_MOSI/I2S2_SD/TIM1_CH3N_76") (pintype "passive"))
    )
    (net (code "154") (name "unconnected-(U1-PC8{slash}TIM8_CH3{slash}SDIO_D0-Pad98)") (class "Default")
      (node (ref "U1") (pin "98") (pinfunction "PC8/TIM8_CH3/SDIO_D0_98") (pintype "passive"))
    )
    (net (code "155") (name "unconnected-(U1-PC9{slash}TIM8_CH4{slash}SDIO_D1-Pad99)") (class "Default")
      (node (ref "U1") (pin "99") (pinfunction "PC9/TIM8_CH4/SDIO_D1_99") (pintype "passive"))
    )
    (net (code "156") (name "unconnected-(U1-PC10{slash}UART4_TX{slash}SDIO_D2-Pad111)") (class "Default")
      (node (ref "U1") (pin "111") (pinfunction "PC10/UART4_TX/SDIO_D2_111") (pintype "passive"))
    )
    (net (code "157") (name "unconnected-(U1-PC11{slash}UART4_RX{slash}SDIO_D3-Pad112)") (class "Default")
      (node (ref "U1") (pin "112") (pinfunction "PC11/UART4_RX/SDIO_D3_112") (pintype "passive"))
    )
    (net (code "158") (name "unconnected-(U1-PC12{slash}UART5_TX{slash}SDIO_CK-Pad113)") (class "Default")
      (node (ref "U1") (pin "113") (pinfunction "PC12/UART5_TX/SDIO_CK_113") (pintype "passive"))
    )
    (net (code "159") (name "unconnected-(U1-PC13-TAMPER-RTC-Pad7)") (class "Default")
      (node (ref "U1") (pin "7") (pinfunction "PC13-TAMPER-RTC_7") (pintype "passive"))
    )
    (net (code "160") (name "unconnected-(U1-PD2{slash}TIM3_ETR{slash}UART5_RX{slash}SDIO_CMD-Pad116)") (class "Default")
      (node (ref "U1") (pin "116") (pinfunction "PD2/TIM3_ETR/UART5_RX/SDIO_CMD_116") (pintype "passive"))
    )
    (net (code "161") (name "unconnected-(U1-PD7{slash}FSMC_NE1{slash}FSMC_NCE2-Pad123)") (class "Default")
      (node (ref "U1") (pin "123") (pinfunction "PD7/FSMC_NE1/FSMC_NCE2_123") (pintype "passive"))
    )
    (net (code "162") (name "unconnected-(U1-PE4{slash}TRACED1{slash}FSMC_A20-Pad3)") (class "Default")
      (node (ref "U1") (pin "3") (pinfunction "PE4/TRACED1/FSMC_A20_3") (pintype "passive"))
    )
    (net (code "163") (name "unconnected-(U1-PE6{slash}TRACED3{slash}FSMC_A22-Pad5)") (class "Default")
      (node (ref "U1") (pin "5") (pinfunction "PE6/TRACED3/FSMC_A22_5") (pintype "passive"))
    )
    (net (code "164") (name "unconnected-(U1-PF6{slash}ADC3_IN4{slash}FSMC_NIORD-Pad18)") (class "Default")
      (node (ref "U1") (pin "18") (pinfunction "PF6/ADC3_IN4/FSMC_NIORD_18") (pintype "passive"))
    )
    (net (code "165") (name "unconnected-(U1-PF7{slash}ADC3_IN5{slash}FSMC_NREG-Pad19)") (class "Default")
      (node (ref "U1") (pin "19") (pinfunction "PF7/ADC3_IN5/FSMC_NREG_19") (pintype "passive"))
    )
    (net (code "166") (name "unconnected-(U1-PF8{slash}ADC3_IN6{slash}FSMC_NIOWR-Pad20)") (class "Default")
      (node (ref "U1") (pin "20") (pinfunction "PF8/ADC3_IN6/FSMC_NIOWR_20") (pintype "passive"))
    )
    (net (code "167") (name "unconnected-(U1-PG6{slash}FSMC_INT2-Pad91)") (class "Default")
      (node (ref "U1") (pin "91") (pinfunction "PG6/FSMC_INT2_91") (pintype "passive"))
    )
    (net (code "168") (name "unconnected-(U1-PG7{slash}FSMC_INT3-Pad92)") (class "Default")
      (node (ref "U1") (pin "92") (pinfunction "PG7/FSMC_INT3_92") (pintype "passive"))
    )
    (net (code "169") (name "unconnected-(U1-PG8-Pad93)") (class "Default")
      (node (ref "U1") (pin "93") (pinfunction "PG8_93") (pintype "passive"))
    )
    (net (code "170") (name "unconnected-(U1-PG9{slash}FSMC_NE2{slash}FSMC_NCE3-Pad124)") (class "Default")
      (node (ref "U1") (pin "124") (pinfunction "PG9/FSMC_NE2/FSMC_NCE3_124") (pintype "passive"))
    )
    (net (code "171") (name "unconnected-(U1-PG10{slash}FSMC_NCE4_1{slash}FSMC_NE3-Pad125)") (class "Default")
      (node (ref "U1") (pin "125") (pinfunction "PG10/FSMC_NCE4_1/FSMC_NE3_125") (pintype "passive"))
    )
    (net (code "172") (name "unconnected-(U1-PG11{slash}FSMC_NCE4_2-Pad126)") (class "Default")
      (node (ref "U1") (pin "126") (pinfunction "PG11/FSMC_NCE4_2_126") (pintype "passive"))
    )
    (net (code "173") (name "unconnected-(U6-PHY_RX+-Pad11)") (class "Default")
      (node (ref "U6") (pin "11") (pinfunction "PHY_RX+_11") (pintype "passive"))
    )
    (net (code "174") (name "unconnected-(U6-PHY_RX--Pad12)") (class "Default")
      (node (ref "U6") (pin "12") (pinfunction "PHY_RX-_12") (pintype "passive"))
    )
    (net (code "175") (name "unconnected-(U6-PHY_TX+-Pad13)") (class "Default")
      (node (ref "U6") (pin "13") (pinfunction "PHY_TX+_13") (pintype "passive"))
    )
    (net (code "176") (name "unconnected-(U6-PHY_TX--Pad14)") (class "Default")
      (node (ref "U6") (pin "14") (pinfunction "PHY_TX-_14") (pintype "passive"))
    )
    (net (code "177") (name "unconnected-(U6-UART_CRS-Pad6)") (class "Default")
      (node (ref "U6") (pin "6") (pinfunction "UART_CRS_6") (pintype "passive"))
    )
    (net (code "178") (name "unconnected-(U6-UART_TRS-Pad5)") (class "Default")
      (node (ref "U6") (pin "5") (pinfunction "UART_TRS_5") (pintype "passive"))
    )
    (net (code "179") (name "unconnected-(U8-CTS#-Pad9)") (class "Default")
      (node (ref "U8") (pin "9") (pinfunction "CTS#_9") (pintype "passive"))
    )
    (net (code "180") (name "unconnected-(U8-DCD#-Pad12)") (class "Default")
      (node (ref "U8") (pin "12") (pinfunction "DCD#_12") (pintype "passive"))
    )
    (net (code "181") (name "unconnected-(U8-DSR#-Pad10)") (class "Default")
      (node (ref "U8") (pin "10") (pinfunction "DSR#_10") (pintype "passive"))
    )
    (net (code "182") (name "unconnected-(U8-R232-Pad15)") (class "Default")
      (node (ref "U8") (pin "15") (pinfunction "R232_15") (pintype "passive"))
    )
    (net (code "183") (name "unconnected-(U8-RI#-Pad11)") (class "Default")
      (node (ref "U8") (pin "11") (pinfunction "RI#_11") (pintype "passive"))
    )
    (net (code "184") (name "unconnected-(USB_232-NC-Pad4)") (class "Default")
      (node (ref "USB_232") (pin "4") (pinfunction "NC_4") (pintype "passive"))
    )
  )
)
